# Zero_V1_0.net
KiCad netlist of a schematic drawn in EAGLE
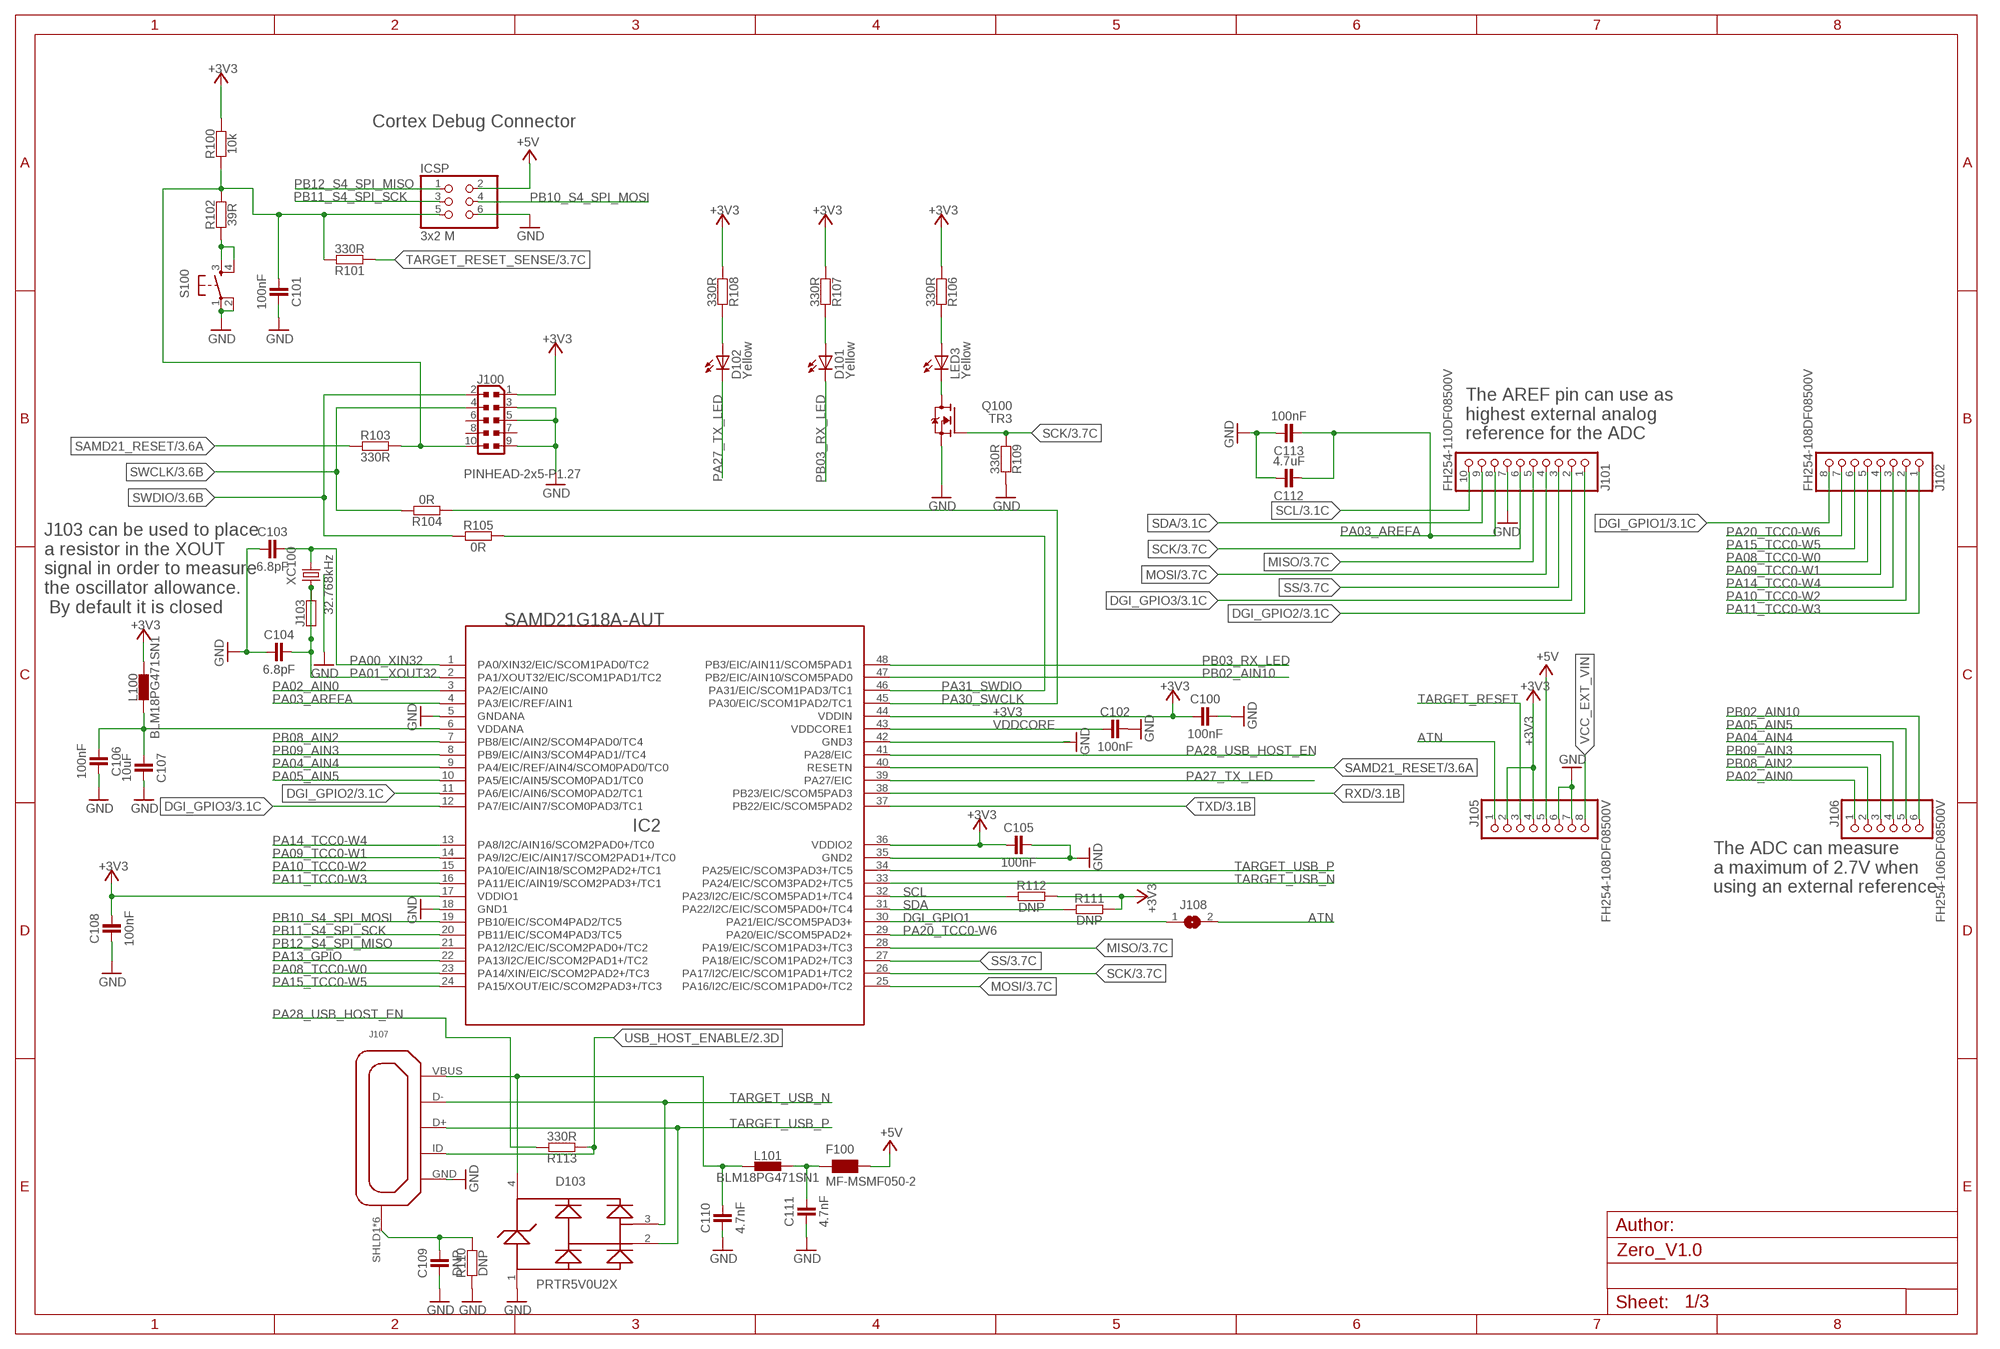
[diagram p0: schematic, sheet 1]
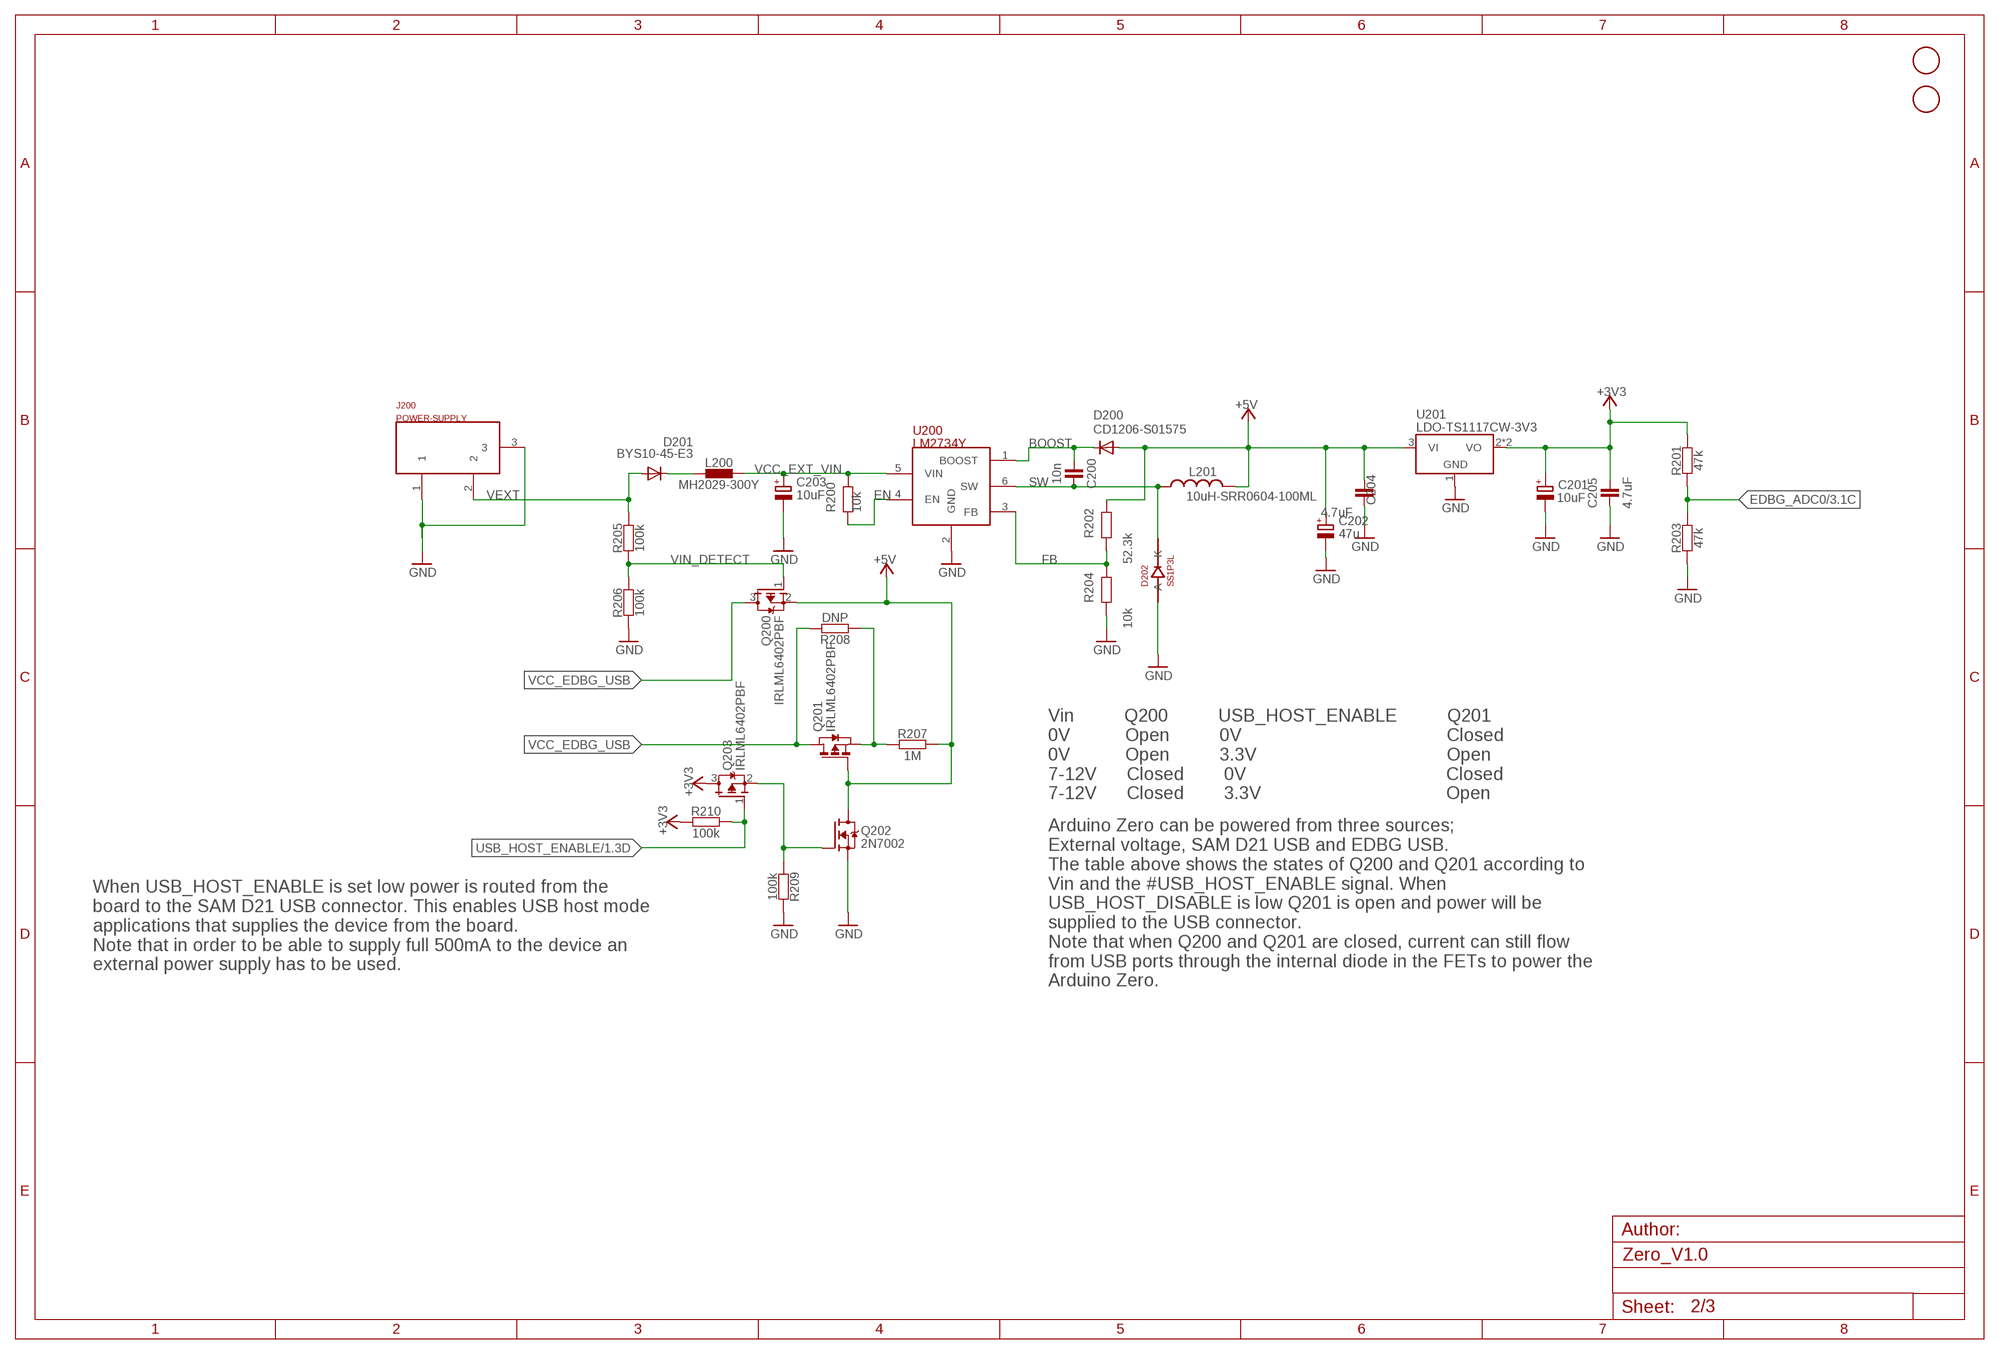
[diagram p1: schematic, sheet 2]
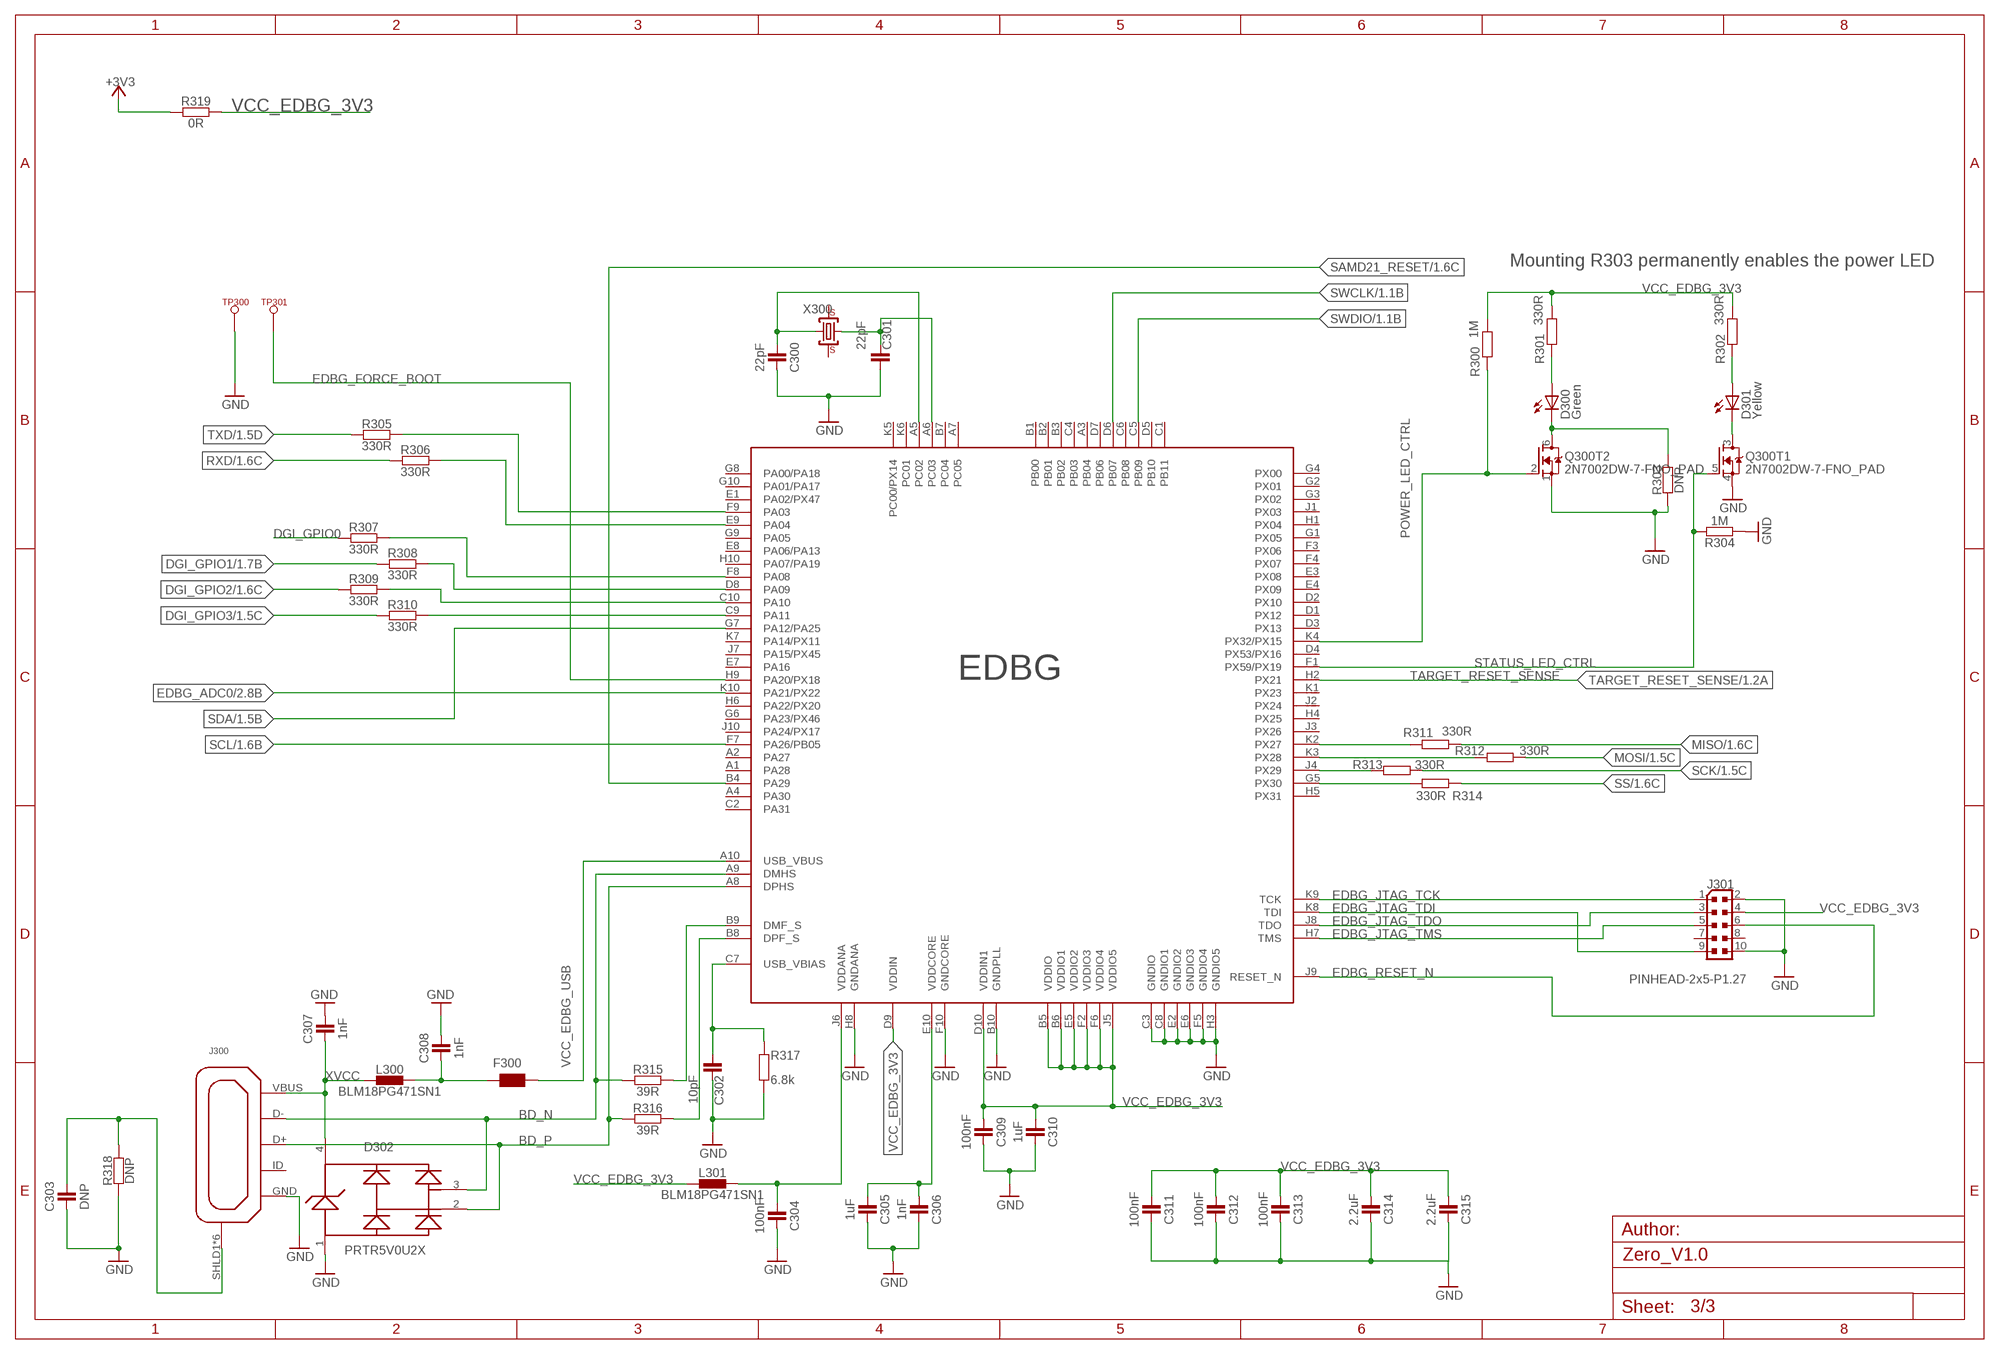
[diagram p2: schematic, sheet 3]

(export (version "E")
  (design (tool "Eeschema 10.0.6"))
  (components
    (comp (ref "C200")
      (value "10n")
      (footprint "eagle-import:C0402")
      (libsource (lib "eagle-import") (part "CAPACITORS-0402"))
    )
    (comp (ref "C201")
      (value "10uF")
      (footprint "eagle-import:PANASONIC_D")
      (fields (field (name "PART_NUMBER") "47uF"))
      (libsource (lib "eagle-import") (part "0113_47UF"))
    )
    (comp (ref "C202")
      (value "47u")
      (footprint "eagle-import:PANASONIC_D")
      (fields (field (name "PART_NUMBER") "47uF"))
      (libsource (lib "eagle-import") (part "0113_47UF"))
    )
    (comp (ref "C203")
      (value "10uF")
      (footprint "eagle-import:PANASONIC_D")
      (fields (field (name "PART_NUMBER") "47uF"))
      (libsource (lib "eagle-import") (part "0113_47UF"))
    )
    (comp (ref "C204")
      (value "4.7uF")
      (footprint "eagle-import:C0603")
      (libsource (lib "eagle-import") (part "CAPACITORS-0603"))
    )
    (comp (ref "C205")
      (value "4.7uF")
      (footprint "eagle-import:C0603")
      (libsource (lib "eagle-import") (part "CAPACITORS-0603"))
    )
    (comp (ref "D200")
      (value "CD1206-S01575")
      (footprint "eagle-import:MINIMELF")
      (libsource (lib "eagle-import") (part "0012_CD1206-S01575"))
    )
    (comp (ref "D201")
      (value "BYS10-45-E3")
      (footprint "eagle-import:MINIMELF")
      (fields (field (name "PART_NUMBER") "CD1206-S01575"))
      (libsource (lib "eagle-import") (part "0012_CD1206-S01575"))
    )
    (comp (ref "D202")
      (value "SS1P3L")
      (footprint "eagle-import:DO220AAL")
      (fields (field (name "PART_NUMBER") "SS1P3L-M3/84A"))
      (libsource (lib "eagle-import") (part "0025_SS1P3L-M3/84A"))
    )
    (comp (ref "FD1")
      (value "FIDUCIALMOUNT")
      (footprint "eagle-import:FIDUCIA-MOUNT")
      (libsource (lib "eagle-import") (part "FIDUCIALMOUNT"))
    )
    (comp (ref "FD2")
      (value "FIDUCIALMOUNT")
      (footprint "eagle-import:FIDUCIA-MOUNT")
      (libsource (lib "eagle-import") (part "FIDUCIALMOUNT"))
    )
    (comp (ref "J200")
      (value "POWER-SUPPLY")
      (footprint "eagle-import:POWERSUPPLY_DC-21MM")
      (fields (field (name "PART_NUMBER") "19746"))
      (libsource (lib "eagle-import") (part "0018_19746-POWER-SUPPLY"))
    )
    (comp (ref "L200")
      (value "MH2029-300Y")
      (footprint "eagle-import:C0805")
      (libsource (lib "eagle-import") (part "INDUCTOR-0805"))
    )
    (comp (ref "L201")
      (value "10uH-SRR0604-100ML")
      (footprint "eagle-import:SRR0604")
      (fields (field (name "PART_NUMBER") "SRR0604-100ML"))
      (libsource (lib "eagle-import") (part "0031_SRR0604-100ML"))
    )
    (comp (ref "Q200")
      (value "IRLML6402PBF")
      (footprint "eagle-import:SOT323")
      (libsource (lib "eagle-import") (part "IRLML6402PBF"))
    )
    (comp (ref "Q201")
      (value "IRLML6402PBF")
      (footprint "eagle-import:SOT-23")
      (fields (field (name "PART_NUMBER") "PMV48XP"))
      (libsource (lib "eagle-import") (part "0297_PMV48XP"))
    )
    (comp (ref "Q202")
      (value "2N7002")
      (footprint "eagle-import:SOT23")
      (libsource (lib "eagle-import") (part "MOSFET-N-SOT23"))
    )
    (comp (ref "Q203")
      (value "IRLML6402PBF")
      (footprint "eagle-import:SOT323")
      (libsource (lib "eagle-import") (part "IRLML6402PBF"))
    )
    (comp (ref "R200")
      (value "10k")
      (footprint "eagle-import:C0402")
      (libsource (lib "eagle-import") (part "RESISTORS-0402"))
    )
    (comp (ref "R201")
      (value "47k")
      (footprint "eagle-import:C0402")
      (libsource (lib "eagle-import") (part "RESISTORS-0402"))
    )
    (comp (ref "R202")
      (value "52.3k")
      (footprint "eagle-import:C0402")
      (libsource (lib "eagle-import") (part "RESISTORS-0402"))
    )
    (comp (ref "R203")
      (value "47k")
      (footprint "eagle-import:C0402")
      (libsource (lib "eagle-import") (part "RESISTORS-0402"))
    )
    (comp (ref "R204")
      (value "10k")
      (footprint "eagle-import:C0402")
      (libsource (lib "eagle-import") (part "RESISTORS-0402"))
    )
    (comp (ref "R205")
      (value "100k")
      (footprint "eagle-import:C0402")
      (libsource (lib "eagle-import") (part "RESISTORS-0402"))
    )
    (comp (ref "R206")
      (value "100k")
      (footprint "eagle-import:C0402")
      (libsource (lib "eagle-import") (part "RESISTORS-0402"))
    )
    (comp (ref "R207")
      (value "1M")
      (footprint "eagle-import:C0402")
      (libsource (lib "eagle-import") (part "RESISTORS-0402"))
    )
    (comp (ref "R208")
      (value "DNP")
      (footprint "eagle-import:C0402")
      (libsource (lib "eagle-import") (part "RESISTORS-0402"))
    )
    (comp (ref "R209")
      (value "100k")
      (footprint "eagle-import:C0402")
      (libsource (lib "eagle-import") (part "RESISTORS-0402"))
    )
    (comp (ref "R210")
      (value "100k")
      (footprint "eagle-import:C0402")
      (libsource (lib "eagle-import") (part "RESISTORS-0402"))
    )
    (comp (ref "U200")
      (value "LM2734Y")
      (footprint "eagle-import:SOT23-6")
      (fields (field (name "PART_NUMBER") "LM2734YMK"))
      (libsource (lib "eagle-import") (part "0179_LM2734YMK"))
    )
    (comp (ref "U201")
      (value "LDO-TS1117CW-3V3")
      (footprint "eagle-import:SOT223")
      (libsource (lib "eagle-import") (part "LDO-TS1117CW-3V3"))
    )
    (comp (ref "C100")
      (value "100nF")
      (footprint "eagle-import:C0402")
      (libsource (lib "eagle-import") (part "CAPACITORS-0402"))
    )
    (comp (ref "C101")
      (value "100nF")
      (footprint "eagle-import:C0402")
      (libsource (lib "eagle-import") (part "CAPACITORS-0402"))
    )
    (comp (ref "C102")
      (value "100nF")
      (footprint "eagle-import:C0402")
      (libsource (lib "eagle-import") (part "CAPACITORS-0402"))
    )
    (comp (ref "C103")
      (value "6.8pF")
      (footprint "eagle-import:C0402")
      (libsource (lib "eagle-import") (part "CAPACITORS-0402"))
    )
    (comp (ref "C104")
      (value "6.8pF")
      (footprint "eagle-import:C0402")
      (libsource (lib "eagle-import") (part "CAPACITORS-0402"))
    )
    (comp (ref "C105")
      (value "100nF")
      (footprint "eagle-import:C0402")
      (libsource (lib "eagle-import") (part "CAPACITORS-0402"))
    )
    (comp (ref "C106")
      (value "100nF")
      (footprint "eagle-import:C0402")
      (libsource (lib "eagle-import") (part "CAPACITORS-0402"))
    )
    (comp (ref "C107")
      (value "10uF")
      (footprint "eagle-import:C0603")
      (libsource (lib "eagle-import") (part "CAPACITORS-0603"))
    )
    (comp (ref "C108")
      (value "100nF")
      (footprint "eagle-import:C0402")
      (libsource (lib "eagle-import") (part "CAPACITORS-0402"))
    )
    (comp (ref "C109")
      (value "DNP")
      (footprint "eagle-import:C0402")
      (libsource (lib "eagle-import") (part "CAPACITORS-0402"))
    )
    (comp (ref "C110")
      (value "4.7nF")
      (footprint "eagle-import:C0402")
      (libsource (lib "eagle-import") (part "CAPACITORS-0402"))
    )
    (comp (ref "C111")
      (value "4.7nF")
      (footprint "eagle-import:C0402")
      (libsource (lib "eagle-import") (part "CAPACITORS-0402"))
    )
    (comp (ref "C112")
      (value "4.7uF")
      (footprint "eagle-import:C0603")
      (libsource (lib "eagle-import") (part "CAPACITORS-0603"))
    )
    (comp (ref "C113")
      (value "100nF")
      (footprint "eagle-import:C0402")
      (libsource (lib "eagle-import") (part "CAPACITORS-0402"))
    )
    (comp (ref "D101")
      (value "Yellow")
      (footprint "eagle-import:CHIPLED_0805")
      (fields (field (name "PART_NUMBER") "KPT-2012YC"))
      (libsource (lib "eagle-import") (part "0044_KPT-2012YC"))
    )
    (comp (ref "D102")
      (value "Yellow")
      (footprint "eagle-import:CHIPLED_0805")
      (fields (field (name "PART_NUMBER") "KPT-2012YC"))
      (libsource (lib "eagle-import") (part "0044_KPT-2012YC"))
    )
    (comp (ref "D103")
      (value "PRTR5V0U2XB")
      (footprint "eagle-import:SOT143B")
      (libsource (lib "eagle-import") (part "PRTR5V0U2XB"))
    )
    (comp (ref "F100")
      (value "MF-MSMF050-2")
      (footprint "eagle-import:WUERTH-ELEKTRONIK_1812")
      (libsource (lib "eagle-import") (part "WUERTH-ELEKTRONIK_WE-CBF_1812"))
    )
    (comp (ref "IC2")
      (value "SAMD21G18A-AUT")
      (footprint "eagle-import:TQFP48")
      (libsource (lib "eagle-import") (part "SAMD21G18A"))
    )
    (comp (ref "ICSP")
      (value "3x2 M")
      (footprint "eagle-import:2X03")
      (libsource (lib "eagle-import") (part "ICSP"))
    )
    (comp (ref "J100")
      (value "PINHEAD-2x5-P1.27")
      (footprint "eagle-import:PINHEAD_2X05_127")
      (libsource (lib "eagle-import") (part "0171_PH127-205DF055G00AROUND-PADS"))
    )
    (comp (ref "J101")
      (value "FH254-110DF08500V")
      (footprint "eagle-import:1X10")
      (fields (field (name "PART_NUMBER") "20TW-537"))
      (libsource (lib "eagle-import") (part "1684_20TW-537"))
    )
    (comp (ref "J102")
      (value "FH254-108DF08500V")
      (footprint "eagle-import:1X08")
      (fields (field (name "PART_NUMBER") "20TW-536"))
      (libsource (lib "eagle-import") (part "1683_20TW-536"))
    )
    (comp (ref "J103")
      (value "RESISTORS-0402")
      (footprint "eagle-import:C0402")
      (libsource (lib "eagle-import") (part "RESISTORS-0402"))
    )
    (comp (ref "J105")
      (value "FH254-108DF08500V")
      (footprint "eagle-import:1X08")
      (fields (field (name "PART_NUMBER") "20TW-536"))
      (libsource (lib "eagle-import") (part "1683_20TW-536"))
    )
    (comp (ref "J106")
      (value "FH254-106DF08500V")
      (footprint "eagle-import:1X06")
      (fields (field (name "PART_NUMBER") "20TW-535"))
      (libsource (lib "eagle-import") (part "1682_20TW-535_STD"))
    )
    (comp (ref "J107")
      (value "ZX62-AB-5PA")
      (footprint "eagle-import:USB-MICRO-10103594")
      (libsource (lib "eagle-import") (part "ZX62-AB-5PA"))
    )
    (comp (ref "J108")
      (value "SJ")
      (footprint "eagle-import:SJ")
      (libsource (lib "eagle-import") (part "SJ"))
    )
    (comp (ref "L100")
      (value "BLM18PG471SN1")
      (footprint "eagle-import:C0603")
      (libsource (lib "eagle-import") (part "INDUCTOR-0603"))
    )
    (comp (ref "L101")
      (value "BLM18PG471SN1")
      (footprint "eagle-import:C0603")
      (libsource (lib "eagle-import") (part "INDUCTOR-0603"))
    )
    (comp (ref "LED3")
      (value "Yellow")
      (footprint "eagle-import:CHIPLED_0805")
      (fields (field (name "PART_NUMBER") "KPT-2012YC"))
      (libsource (lib "eagle-import") (part "0044_KPT-2012YC"))
    )
    (comp (ref "R100")
      (value "10k")
      (footprint "eagle-import:C0402")
      (libsource (lib "eagle-import") (part "RESISTORS-0402"))
    )
    (comp (ref "R101")
      (value "330R")
      (footprint "eagle-import:C0402")
      (libsource (lib "eagle-import") (part "RESISTORS-0402"))
    )
    (comp (ref "R102")
      (value "39R")
      (footprint "eagle-import:C0402")
      (libsource (lib "eagle-import") (part "RESISTORS-0402"))
    )
    (comp (ref "R103")
      (value "330R")
      (footprint "eagle-import:C0402")
      (libsource (lib "eagle-import") (part "RESISTORS-0402"))
    )
    (comp (ref "R104")
      (value "0R")
      (footprint "eagle-import:C0402")
      (libsource (lib "eagle-import") (part "RESISTORS-0402"))
    )
    (comp (ref "R105")
      (value "0R")
      (footprint "eagle-import:C0402")
      (libsource (lib "eagle-import") (part "RESISTORS-0402"))
    )
    (comp (ref "R106")
      (value "330R")
      (footprint "eagle-import:C0402")
      (libsource (lib "eagle-import") (part "RESISTORS-0402"))
    )
    (comp (ref "R107")
      (value "330R")
      (footprint "eagle-import:C0402")
      (libsource (lib "eagle-import") (part "RESISTORS-0402"))
    )
    (comp (ref "R108")
      (value "330R")
      (footprint "eagle-import:C0402")
      (libsource (lib "eagle-import") (part "RESISTORS-0402"))
    )
    (comp (ref "R109")
      (value "330R")
      (footprint "eagle-import:C0402")
      (libsource (lib "eagle-import") (part "RESISTORS-0402"))
    )
    (comp (ref "R110")
      (value "DNP")
      (footprint "eagle-import:C0402")
      (libsource (lib "eagle-import") (part "RESISTORS-0402"))
    )
    (comp (ref "R111")
      (value "DNP")
      (footprint "eagle-import:C0402")
      (libsource (lib "eagle-import") (part "RESISTORS-0402"))
    )
    (comp (ref "R112")
      (value "DNP")
      (footprint "eagle-import:C0402")
      (libsource (lib "eagle-import") (part "RESISTORS-0402"))
    )
    (comp (ref "R113")
      (value "330R")
      (footprint "eagle-import:C0402")
      (libsource (lib "eagle-import") (part "RESISTORS-0402"))
    )
    (comp (ref "S100")
      (value "PUSHBUTTON3")
      (footprint "eagle-import:TS42_4PINS")
      (libsource (lib "eagle-import") (part "PUSHBUTTON3"))
    )
    (comp (ref "TR3")
      (value "Q100")
      (footprint "eagle-import:SOT-23")
      (libsource (lib "eagle-import") (part "1612_2N7002LT1G"))
    )
    (comp (ref "XC100")
      (value "32.768kHz")
      (footprint "eagle-import:CRYSTAL_TC26SMD")
      (libsource (lib "eagle-import") (part "CRYSTALSMD"))
    )
    (comp (ref "C300")
      (value "22pF")
      (footprint "eagle-import:C0402")
      (libsource (lib "eagle-import") (part "CAPACITORS-0402"))
    )
    (comp (ref "C301")
      (value "22pF")
      (footprint "eagle-import:C0402")
      (libsource (lib "eagle-import") (part "CAPACITORS-0402"))
    )
    (comp (ref "C302")
      (value "10pF")
      (footprint "eagle-import:C0402")
      (libsource (lib "eagle-import") (part "CAPACITORS-0402"))
    )
    (comp (ref "C303")
      (value "DNP")
      (footprint "eagle-import:C0402")
      (libsource (lib "eagle-import") (part "CAPACITORS-0402"))
    )
    (comp (ref "C304")
      (value "100nF")
      (footprint "eagle-import:C0402")
      (libsource (lib "eagle-import") (part "CAPACITORS-0402"))
    )
    (comp (ref "C305")
      (value "1uF")
      (footprint "eagle-import:C0402")
      (libsource (lib "eagle-import") (part "CAPACITORS-0402"))
    )
    (comp (ref "C306")
      (value "1nF")
      (footprint "eagle-import:C0402")
      (libsource (lib "eagle-import") (part "CAPACITORS-0402"))
    )
    (comp (ref "C307")
      (value "1nF")
      (footprint "eagle-import:C0402")
      (libsource (lib "eagle-import") (part "CAPACITORS-0402"))
    )
    (comp (ref "C308")
      (value "1nF")
      (footprint "eagle-import:C0402")
      (libsource (lib "eagle-import") (part "CAPACITORS-0402"))
    )
    (comp (ref "C309")
      (value "100nF")
      (footprint "eagle-import:C0402")
      (libsource (lib "eagle-import") (part "CAPACITORS-0402"))
    )
    (comp (ref "C310")
      (value "1uF")
      (footprint "eagle-import:C0402")
      (libsource (lib "eagle-import") (part "CAPACITORS-0402"))
    )
    (comp (ref "C311")
      (value "100nF")
      (footprint "eagle-import:C0402")
      (libsource (lib "eagle-import") (part "CAPACITORS-0402"))
    )
    (comp (ref "C312")
      (value "100nF")
      (footprint "eagle-import:C0402")
      (libsource (lib "eagle-import") (part "CAPACITORS-0402"))
    )
    (comp (ref "C313")
      (value "100nF")
      (footprint "eagle-import:C0402")
      (libsource (lib "eagle-import") (part "CAPACITORS-0402"))
    )
    (comp (ref "C314")
      (value "2.2uF")
      (footprint "eagle-import:C0402")
      (libsource (lib "eagle-import") (part "CAPACITORS-0402"))
    )
    (comp (ref "C315")
      (value "2.2uF")
      (footprint "eagle-import:C0402")
      (libsource (lib "eagle-import") (part "CAPACITORS-0402"))
    )
    (comp (ref "D300")
      (value "Green")
      (footprint "eagle-import:CHIPLED_0805")
      (fields (field (name "PART_NUMBER") "KPT-2012SGC"))
      (libsource (lib "eagle-import") (part "0043_KPT-2012SGC"))
    )
    (comp (ref "D301")
      (value "Yellow")
      (footprint "eagle-import:CHIPLED_0805")
      (fields (field (name "PART_NUMBER") "KPT-2012SGC"))
      (libsource (lib "eagle-import") (part "0043_KPT-2012SGC"))
    )
    (comp (ref "D302")
      (value "PRTR5V0U2XB")
      (footprint "eagle-import:SOT143B")
      (libsource (lib "eagle-import") (part "PRTR5V0U2XB"))
    )
    (comp (ref "EDBG")
      (value "EDBG")
      (footprint "eagle-import:VFBGA100")
      (libsource (lib "eagle-import") (part "EDBG"))
    )
    (comp (ref "F300")
      (value "WUERTH-ELEKTRONIK_WE-CBF_1812")
      (footprint "eagle-import:WUERTH-ELEKTRONIK_1812")
      (libsource (lib "eagle-import") (part "WUERTH-ELEKTRONIK_WE-CBF_1812"))
    )
    (comp (ref "J300")
      (value "ZX62-AB-5PA")
      (footprint "eagle-import:USB-MICRO-10103594")
      (libsource (lib "eagle-import") (part "ZX62-AB-5PA"))
    )
    (comp (ref "J301")
      (value "PINHEAD-2x5-P1.27")
      (footprint "eagle-import:PINHEAD_2X05_127")
      (libsource (lib "eagle-import") (part "0171_PH127-205DF055G00AROUND-PADS"))
    )
    (comp (ref "L300")
      (value "BLM18PG471SN1")
      (footprint "eagle-import:C0603")
      (libsource (lib "eagle-import") (part "INDUCTOR-0603"))
    )
    (comp (ref "L301")
      (value "BLM18PG471SN1")
      (footprint "eagle-import:C0603")
      (libsource (lib "eagle-import") (part "INDUCTOR-0603"))
    )
    (comp (ref "Q300")
      (value "2N7002DW-7-FNO_PAD")
      (footprint "eagle-import:PWR_SC70-6L2")
      (libsource (lib "eagle-import") (part "2N7002DW-7-FNO_PAD"))
    )
    (comp (ref "R300")
      (value "1M")
      (footprint "eagle-import:C0402")
      (libsource (lib "eagle-import") (part "RESISTORS-0402"))
    )
    (comp (ref "R301")
      (value "330R")
      (footprint "eagle-import:C0402")
      (libsource (lib "eagle-import") (part "RESISTORS-0402"))
    )
    (comp (ref "R302")
      (value "330R")
      (footprint "eagle-import:C0402")
      (libsource (lib "eagle-import") (part "RESISTORS-0402"))
    )
    (comp (ref "R303")
      (value "DNP")
      (footprint "eagle-import:C0402")
      (libsource (lib "eagle-import") (part "RESISTORS-0402"))
    )
    (comp (ref "R304")
      (value "1M")
      (footprint "eagle-import:C0402")
      (libsource (lib "eagle-import") (part "RESISTORS-0402"))
    )
    (comp (ref "R305")
      (value "330R")
      (footprint "eagle-import:C0402")
      (libsource (lib "eagle-import") (part "RESISTORS-0402"))
    )
    (comp (ref "R306")
      (value "330R")
      (footprint "eagle-import:C0402")
      (libsource (lib "eagle-import") (part "RESISTORS-0402"))
    )
    (comp (ref "R307")
      (value "330R")
      (footprint "eagle-import:C0402")
      (libsource (lib "eagle-import") (part "RESISTORS-0402"))
    )
    (comp (ref "R308")
      (value "330R")
      (footprint "eagle-import:C0402")
      (libsource (lib "eagle-import") (part "RESISTORS-0402"))
    )
    (comp (ref "R309")
      (value "330R")
      (footprint "eagle-import:C0402")
      (libsource (lib "eagle-import") (part "RESISTORS-0402"))
    )
    (comp (ref "R310")
      (value "330R")
      (footprint "eagle-import:C0402")
      (libsource (lib "eagle-import") (part "RESISTORS-0402"))
    )
    (comp (ref "R311")
      (value "330R")
      (footprint "eagle-import:C0402")
      (libsource (lib "eagle-import") (part "RESISTORS-0402"))
    )
    (comp (ref "R312")
      (value "330R")
      (footprint "eagle-import:C0402")
      (libsource (lib "eagle-import") (part "RESISTORS-0402"))
    )
    (comp (ref "R313")
      (value "330R")
      (footprint "eagle-import:C0402")
      (libsource (lib "eagle-import") (part "RESISTORS-0402"))
    )
    (comp (ref "R314")
      (value "330R")
      (footprint "eagle-import:C0402")
      (libsource (lib "eagle-import") (part "RESISTORS-0402"))
    )
    (comp (ref "R315")
      (value "39R")
      (footprint "eagle-import:C0402")
      (libsource (lib "eagle-import") (part "RESISTORS-0402"))
    )
    (comp (ref "R316")
      (value "39R")
      (footprint "eagle-import:C0402")
      (libsource (lib "eagle-import") (part "RESISTORS-0402"))
    )
    (comp (ref "R317")
      (value "6.8k")
      (footprint "eagle-import:C0402")
      (libsource (lib "eagle-import") (part "RESISTORS-0402"))
    )
    (comp (ref "R318")
      (value "DNP")
      (footprint "eagle-import:C0402")
      (libsource (lib "eagle-import") (part "RESISTORS-0402"))
    )
    (comp (ref "R319")
      (value "0R")
      (footprint "eagle-import:C0402")
      (libsource (lib "eagle-import") (part "RESISTORS-0402"))
    )
    (comp (ref "TP300")
      (value "TP_SP")
      (footprint "eagle-import:TP-SP")
      (libsource (lib "eagle-import") (part "TP_SP"))
    )
    (comp (ref "TP301")
      (value "TP_SP")
      (footprint "eagle-import:TP-SP")
      (libsource (lib "eagle-import") (part "TP_SP"))
    )
    (comp (ref "X300")
      (value "12mHz-12pF-K7")
      (footprint "eagle-import:CRYSTAL-5.4-3.2")
      (libsource (lib "eagle-import") (part "12MHZ-12PF-K75.4-3.2"))
    )
  )
  (nets
    (net (code "1") (name "+3V3") (class "Default")
      (node (ref "C100") (pin "1") (pinfunction "1_1") (pintype "passive"))
      (node (ref "C105") (pin "1") (pinfunction "1_1") (pintype "passive"))
      (node (ref "C108") (pin "2") (pinfunction "2_2") (pintype "passive"))
      (node (ref "C201") (pin "+") (pinfunction "+_+") (pintype "passive"))
      (node (ref "C205") (pin "2") (pinfunction "2_2") (pintype "passive"))
      (node (ref "IC2") (pin "17") (pinfunction "VDDIO1_17") (pintype "power_in"))
      (node (ref "IC2") (pin "36") (pinfunction "VDDIO2_36") (pintype "power_in"))
      (node (ref "IC2") (pin "44") (pinfunction "VDDIN_44") (pintype "power_in"))
      (node (ref "J100") (pin "1") (pinfunction "1_1") (pintype "passive"))
      (node (ref "J105") (pin "2") (pinfunction "2_2") (pintype "passive"))
      (node (ref "J105") (pin "4") (pinfunction "4_4") (pintype "passive"))
      (node (ref "L100") (pin "2") (pinfunction "2_2") (pintype "passive"))
      (node (ref "Q203") (pin "3") (pinfunction "D_3") (pintype "passive"))
      (node (ref "R100") (pin "2") (pinfunction "2_2") (pintype "passive"))
      (node (ref "R106") (pin "1") (pinfunction "1_1") (pintype "passive"))
      (node (ref "R107") (pin "1") (pinfunction "1_1") (pintype "passive"))
      (node (ref "R108") (pin "1") (pinfunction "1_1") (pintype "passive"))
      (node (ref "R111") (pin "2") (pinfunction "2_2") (pintype "passive"))
      (node (ref "R112") (pin "2") (pinfunction "2_2") (pintype "passive"))
      (node (ref "R201") (pin "2") (pinfunction "2_2") (pintype "passive"))
      (node (ref "R210") (pin "1") (pinfunction "1_1") (pintype "passive"))
      (node (ref "R319") (pin "1") (pinfunction "1_1") (pintype "passive"))
      (node (ref "U201") (pin "2") (pinfunction "VO_2") (pintype "passive"))
      (node (ref "U201") (pin "4") (pinfunction "VO_4") (pintype "passive"))
    )
    (net (code "2") (name "+5V") (class "Default")
      (node (ref "C202") (pin "+") (pinfunction "+_+") (pintype "passive"))
      (node (ref "C204") (pin "1") (pinfunction "1_1") (pintype "passive"))
      (node (ref "D200") (pin "A") (pinfunction "A_A") (pintype "passive"))
      (node (ref "F100") (pin "2") (pinfunction "2_2") (pintype "passive"))
      (node (ref "ICSP") (pin "2") (pinfunction "2_2") (pintype "passive"))
      (node (ref "J105") (pin "5") (pinfunction "5_5") (pintype "passive"))
      (node (ref "L201") (pin "P$2") (pinfunction "2_P$2") (pintype "passive"))
      (node (ref "Q200") (pin "2") (pinfunction "S_2") (pintype "passive"))
      (node (ref "Q201") (pin "3") (pinfunction "G_3") (pintype "passive"))
      (node (ref "Q202") (pin "3") (pinfunction "D_3") (pintype "passive"))
      (node (ref "R202") (pin "1") (pinfunction "1_1") (pintype "passive"))
      (node (ref "R207") (pin "2") (pinfunction "2_2") (pintype "passive"))
      (node (ref "U201") (pin "3") (pinfunction "VI_3") (pintype "input"))
    )
    (net (code "3") (name "ATN") (class "Default")
      (node (ref "J105") (pin "1") (pinfunction "1_1") (pintype "passive"))
      (node (ref "J108") (pin "2") (pinfunction "2_2") (pintype "passive"))
    )
    (net (code "4") (name "BD_N") (class "Default")
      (node (ref "D302") (pin "3") (pinfunction "3_3") (pintype "bidirectional"))
      (node (ref "EDBG") (pin "A9") (pinfunction "DMHS_A9") (pintype "bidirectional"))
      (node (ref "J300") (pin "D-") (pinfunction "D-_D-") (pintype "bidirectional"))
      (node (ref "R315") (pin "1") (pinfunction "1_1") (pintype "passive"))
    )
    (net (code "5") (name "BD_P") (class "Default")
      (node (ref "D302") (pin "2") (pinfunction "2_2") (pintype "bidirectional"))
      (node (ref "EDBG") (pin "A8") (pinfunction "DPHS_A8") (pintype "bidirectional"))
      (node (ref "J300") (pin "D+") (pinfunction "D+_D+") (pintype "bidirectional"))
      (node (ref "R316") (pin "1") (pinfunction "1_1") (pintype "passive"))
    )
    (net (code "6") (name "BOOST") (class "Default")
      (node (ref "C200") (pin "1") (pinfunction "1_1") (pintype "passive"))
      (node (ref "D200") (pin "C") (pinfunction "C_C") (pintype "passive"))
      (node (ref "U200") (pin "1") (pinfunction "BOOST_1") (pintype "input"))
    )
    (net (code "7") (name "DGI_GPIO0") (class "Default")
      (node (ref "R307") (pin "1") (pinfunction "1_1") (pintype "passive"))
    )
    (net (code "8") (name "DGI_GPIO1") (class "Default")
      (node (ref "IC2") (pin "30") (pinfunction "PA21/EIC/SCOM5PAD3+_30") (pintype "bidirectional"))
      (node (ref "J102") (pin "8") (pinfunction "8_8") (pintype "passive"))
      (node (ref "J108") (pin "1") (pinfunction "1_1") (pintype "passive"))
      (node (ref "R308") (pin "1") (pinfunction "1_1") (pintype "passive"))
    )
    (net (code "9") (name "DGI_GPIO2") (class "Default")
      (node (ref "IC2") (pin "11") (pinfunction "PA6/EIC/AIN6/SCOM0PAD2/TC1_11") (pintype "bidirectional"))
      (node (ref "J101") (pin "1") (pinfunction "1_1") (pintype "passive"))
      (node (ref "R309") (pin "1") (pinfunction "1_1") (pintype "passive"))
    )
    (net (code "10") (name "DGI_GPIO3") (class "Default")
      (node (ref "IC2") (pin "12") (pinfunction "PA7/EIC/AIN7/SCOM0PAD3/TC1_12") (pintype "bidirectional"))
      (node (ref "J101") (pin "2") (pinfunction "2_2") (pintype "passive"))
      (node (ref "R310") (pin "1") (pinfunction "1_1") (pintype "passive"))
    )
    (net (code "11") (name "EDBG_ADC0") (class "Default")
      (node (ref "EDBG") (pin "K10") (pinfunction "PA21/PX22_K10") (pintype "bidirectional"))
      (node (ref "R201") (pin "1") (pinfunction "1_1") (pintype "passive"))
      (node (ref "R203") (pin "2") (pinfunction "2_2") (pintype "passive"))
    )
    (net (code "12") (name "EDBG_FORCE_BOOT") (class "Default")
      (node (ref "EDBG") (pin "H9") (pinfunction "PA20/PX18_H9") (pintype "bidirectional"))
      (node (ref "TP301") (pin "X") (pinfunction "TESTP_X") (pintype "passive"))
    )
    (net (code "13") (name "EDBG_JTAG_TCK") (class "Default")
      (node (ref "EDBG") (pin "K9") (pinfunction "TCK_K9") (pintype "bidirectional"))
      (node (ref "J301") (pin "1") (pinfunction "1_1") (pintype "passive"))
    )
    (net (code "14") (name "EDBG_JTAG_TDI") (class "Default")
      (node (ref "EDBG") (pin "K8") (pinfunction "TDI_K8") (pintype "bidirectional"))
      (node (ref "J301") (pin "9") (pinfunction "9_9") (pintype "passive"))
    )
    (net (code "15") (name "EDBG_JTAG_TDO") (class "Default")
      (node (ref "EDBG") (pin "J8") (pinfunction "TDO_J8") (pintype "bidirectional"))
      (node (ref "J301") (pin "3") (pinfunction "3_3") (pintype "passive"))
    )
    (net (code "16") (name "EDBG_JTAG_TMS") (class "Default")
      (node (ref "EDBG") (pin "H7") (pinfunction "TMS_H7") (pintype "bidirectional"))
      (node (ref "J301") (pin "5") (pinfunction "5_5") (pintype "passive"))
    )
    (net (code "17") (name "EDBG_RESET_N") (class "Default")
      (node (ref "EDBG") (pin "J9") (pinfunction "RESET_N_J9") (pintype "bidirectional"))
      (node (ref "J301") (pin "6") (pinfunction "6_6") (pintype "passive"))
    )
    (net (code "18") (name "EN") (class "Default")
      (node (ref "R200") (pin "2") (pinfunction "2_2") (pintype "passive"))
      (node (ref "U200") (pin "4") (pinfunction "EN_4") (pintype "input"))
    )
    (net (code "19") (name "FB") (class "Default")
      (node (ref "R202") (pin "2") (pinfunction "2_2") (pintype "passive"))
      (node (ref "R204") (pin "1") (pinfunction "1_1") (pintype "passive"))
      (node (ref "U200") (pin "3") (pinfunction "FB_3") (pintype "input"))
    )
    (net (code "20") (name "GND") (class "Default")
      (node (ref "C100") (pin "2") (pinfunction "2_2") (pintype "passive"))
      (node (ref "C101") (pin "2") (pinfunction "2_2") (pintype "passive"))
      (node (ref "C102") (pin "2") (pinfunction "2_2") (pintype "passive"))
      (node (ref "C103") (pin "1") (pinfunction "1_1") (pintype "passive"))
      (node (ref "C104") (pin "1") (pinfunction "1_1") (pintype "passive"))
      (node (ref "C105") (pin "2") (pinfunction "2_2") (pintype "passive"))
      (node (ref "C106") (pin "2") (pinfunction "2_2") (pintype "passive"))
      (node (ref "C107") (pin "2") (pinfunction "2_2") (pintype "passive"))
      (node (ref "C108") (pin "1") (pinfunction "1_1") (pintype "passive"))
      (node (ref "C109") (pin "1") (pinfunction "1_1") (pintype "passive"))
      (node (ref "C110") (pin "1") (pinfunction "1_1") (pintype "passive"))
      (node (ref "C111") (pin "1") (pinfunction "1_1") (pintype "passive"))
      (node (ref "C112") (pin "2") (pinfunction "2_2") (pintype "passive"))
      (node (ref "C113") (pin "2") (pinfunction "2_2") (pintype "passive"))
      (node (ref "C201") (pin "-") (pinfunction "-_-") (pintype "passive"))
      (node (ref "C202") (pin "-") (pinfunction "-_-") (pintype "passive"))
      (node (ref "C203") (pin "-") (pinfunction "-_-") (pintype "passive"))
      (node (ref "C204") (pin "2") (pinfunction "2_2") (pintype "passive"))
      (node (ref "C205") (pin "1") (pinfunction "1_1") (pintype "passive"))
      (node (ref "C300") (pin "2") (pinfunction "2_2") (pintype "passive"))
      (node (ref "C301") (pin "2") (pinfunction "2_2") (pintype "passive"))
      (node (ref "C302") (pin "2") (pinfunction "2_2") (pintype "passive"))
      (node (ref "C303") (pin "1") (pinfunction "1_1") (pintype "passive"))
      (node (ref "C304") (pin "2") (pinfunction "2_2") (pintype "passive"))
      (node (ref "C305") (pin "2") (pinfunction "2_2") (pintype "passive"))
      (node (ref "C306") (pin "2") (pinfunction "2_2") (pintype "passive"))
      (node (ref "C307") (pin "2") (pinfunction "2_2") (pintype "passive"))
      (node (ref "C308") (pin "2") (pinfunction "2_2") (pintype "passive"))
      (node (ref "C309") (pin "2") (pinfunction "2_2") (pintype "passive"))
      (node (ref "C310") (pin "2") (pinfunction "2_2") (pintype "passive"))
      (node (ref "C311") (pin "2") (pinfunction "2_2") (pintype "passive"))
      (node (ref "C312") (pin "2") (pinfunction "2_2") (pintype "passive"))
      (node (ref "C313") (pin "2") (pinfunction "2_2") (pintype "passive"))
      (node (ref "C314") (pin "2") (pinfunction "2_2") (pintype "passive"))
      (node (ref "C315") (pin "2") (pinfunction "2_2") (pintype "passive"))
      (node (ref "D103") (pin "1") (pinfunction "1_1") (pintype "bidirectional"))
      (node (ref "D202") (pin "P$2") (pinfunction "A_P$2") (pintype "bidirectional"))
      (node (ref "D302") (pin "1") (pinfunction "1_1") (pintype "bidirectional"))
      (node (ref "EDBG") (pin "B10") (pinfunction "GNDPLL_B10") (pintype "bidirectional"))
      (node (ref "EDBG") (pin "C3") (pinfunction "GNDIO_C3") (pintype "bidirectional"))
      (node (ref "EDBG") (pin "C8") (pinfunction "GNDIO1_C8") (pintype "bidirectional"))
      (node (ref "EDBG") (pin "E2") (pinfunction "GNDIO2_E2") (pintype "bidirectional"))
      (node (ref "EDBG") (pin "E6") (pinfunction "GNDIO3_E6") (pintype "bidirectional"))
      (node (ref "EDBG") (pin "F10") (pinfunction "GNDCORE_F10") (pintype "bidirectional"))
      (node (ref "EDBG") (pin "F5") (pinfunction "GNDIO4_F5") (pintype "bidirectional"))
      (node (ref "EDBG") (pin "H3") (pinfunction "GNDIO5_H3") (pintype "bidirectional"))
      (node (ref "EDBG") (pin "H8") (pinfunction "GNDANA_H8") (pintype "bidirectional"))
      (node (ref "IC2") (pin "18") (pinfunction "GND1_18") (pintype "power_in"))
      (node (ref "IC2") (pin "35") (pinfunction "GND2_35") (pintype "power_in"))
      (node (ref "IC2") (pin "42") (pinfunction "GND3_42") (pintype "power_in"))
      (node (ref "IC2") (pin "5") (pinfunction "GNDANA_5") (pintype "power_in"))
      (node (ref "ICSP") (pin "6") (pinfunction "6_6") (pintype "passive"))
      (node (ref "J100") (pin "3") (pinfunction "3_3") (pintype "passive"))
      (node (ref "J100") (pin "5") (pinfunction "5_5") (pintype "passive"))
      (node (ref "J100") (pin "9") (pinfunction "9_9") (pintype "passive"))
      (node (ref "J101") (pin "7") (pinfunction "7_7") (pintype "passive"))
      (node (ref "J105") (pin "6") (pinfunction "6_6") (pintype "passive"))
      (node (ref "J105") (pin "7") (pinfunction "7_7") (pintype "passive"))
      (node (ref "J107") (pin "GND") (pinfunction "GND_GND") (pintype "bidirectional"))
      (node (ref "J200") (pin "1") (pinfunction "1_1") (pintype "power_in"))
      (node (ref "J200") (pin "3") (pinfunction "3_3") (pintype "power_in"))
      (node (ref "J300") (pin "GND") (pinfunction "GND_GND") (pintype "bidirectional"))
      (node (ref "J301") (pin "10") (pinfunction "10_10") (pintype "passive"))
      (node (ref "J301") (pin "2") (pinfunction "2_2") (pintype "passive"))
      (node (ref "Q202") (pin "2") (pinfunction "S_2") (pintype "passive"))
      (node (ref "Q300") (pin "1") (pinfunction "S_1") (pintype "passive"))
      (node (ref "Q300") (pin "4") (pinfunction "S_4") (pintype "passive"))
      (node (ref "R109") (pin "2") (pinfunction "2_2") (pintype "passive"))
      (node (ref "R110") (pin "1") (pinfunction "1_1") (pintype "passive"))
      (node (ref "R203") (pin "1") (pinfunction "1_1") (pintype "passive"))
      (node (ref "R204") (pin "2") (pinfunction "2_2") (pintype "passive"))
      (node (ref "R206") (pin "1") (pinfunction "1_1") (pintype "passive"))
      (node (ref "R209") (pin "2") (pinfunction "2_2") (pintype "passive"))
      (node (ref "R303") (pin "1") (pinfunction "1_1") (pintype "passive"))
      (node (ref "R304") (pin "1") (pinfunction "1_1") (pintype "passive"))
      (node (ref "R317") (pin "1") (pinfunction "1_1") (pintype "passive"))
      (node (ref "R318") (pin "1") (pinfunction "1_1") (pintype "passive"))
      (node (ref "S100") (pin "1") (pinfunction "1_1") (pintype "passive"))
      (node (ref "S100") (pin "2") (pinfunction "2_2") (pintype "passive"))
      (node (ref "TP300") (pin "X") (pinfunction "TESTP_X") (pintype "passive"))
      (node (ref "TR3") (pin "2") (pinfunction "S_2") (pintype "passive"))
      (node (ref "U200") (pin "2") (pinfunction "GND_2") (pintype "power_in"))
      (node (ref "U201") (pin "1") (pinfunction "GND_1") (pintype "passive"))
      (node (ref "XC100") (pin "P$1") (pinfunction "GND_P$1") (pintype "bidirectional"))
    )
    (net (code "21") (name "MISO") (class "Default")
      (node (ref "IC2") (pin "28") (pinfunction "PA19/EIC/SCOM1PAD3+/TC3_28") (pintype "bidirectional"))
      (node (ref "J101") (pin "5") (pinfunction "5_5") (pintype "passive"))
      (node (ref "R311") (pin "2") (pinfunction "2_2") (pintype "passive"))
    )
    (net (code "22") (name "MOSI") (class "Default")
      (node (ref "IC2") (pin "25") (pinfunction "PA16/I2C/EIC/SCOM1PAD0+/TC2_25") (pintype "bidirectional"))
      (node (ref "J101") (pin "4") (pinfunction "4_4") (pintype "passive"))
      (node (ref "R312") (pin "2") (pinfunction "2_2") (pintype "passive"))
    )
    (net (code "23") (name "Net-(C109-Pad2)") (class "Default")
      (node (ref "C109") (pin "2") (pinfunction "2_2") (pintype "passive"))
      (node (ref "J107") (pin "SHLD1") (pinfunction "SH_SHLD1") (pintype "bidirectional"))
      (node (ref "J107") (pin "SHLD2") (pinfunction "SH_SHLD2") (pintype "bidirectional"))
      (node (ref "J107") (pin "SHLD3") (pinfunction "SH_SHLD3") (pintype "bidirectional"))
      (node (ref "J107") (pin "SHLD4") (pinfunction "SH_SHLD4") (pintype "bidirectional"))
      (node (ref "J107") (pin "SHLD5") (pinfunction "SH_SHLD5") (pintype "bidirectional"))
      (node (ref "J107") (pin "SHLD6") (pinfunction "SH_SHLD6") (pintype "bidirectional"))
      (node (ref "R110") (pin "2") (pinfunction "2_2") (pintype "passive"))
    )
    (net (code "24") (name "Net-(C111-Pad2)") (class "Default")
      (node (ref "C111") (pin "2") (pinfunction "2_2") (pintype "passive"))
      (node (ref "F100") (pin "1") (pinfunction "1_1") (pintype "passive"))
      (node (ref "L101") (pin "2") (pinfunction "2_2") (pintype "passive"))
    )
    (net (code "25") (name "Net-(C303-Pad2)") (class "Default")
      (node (ref "C303") (pin "2") (pinfunction "2_2") (pintype "passive"))
      (node (ref "J300") (pin "SHLD1") (pinfunction "SH_SHLD1") (pintype "bidirectional"))
      (node (ref "J300") (pin "SHLD2") (pinfunction "SH_SHLD2") (pintype "bidirectional"))
      (node (ref "J300") (pin "SHLD3") (pinfunction "SH_SHLD3") (pintype "bidirectional"))
      (node (ref "J300") (pin "SHLD4") (pinfunction "SH_SHLD4") (pintype "bidirectional"))
      (node (ref "J300") (pin "SHLD5") (pinfunction "SH_SHLD5") (pintype "bidirectional"))
      (node (ref "J300") (pin "SHLD6") (pinfunction "SH_SHLD6") (pintype "bidirectional"))
      (node (ref "R318") (pin "2") (pinfunction "2_2") (pintype "passive"))
    )
    (net (code "26") (name "Net-(C308-Pad1)") (class "Default")
      (node (ref "C308") (pin "1") (pinfunction "1_1") (pintype "passive"))
      (node (ref "F300") (pin "1") (pinfunction "1_1") (pintype "passive"))
      (node (ref "L300") (pin "2") (pinfunction "2_2") (pintype "passive"))
    )
    (net (code "27") (name "Net-(D101-PadA)") (class "Default")
      (node (ref "D101") (pin "A") (pinfunction "A_A") (pintype "passive"))
      (node (ref "R107") (pin "2") (pinfunction "2_2") (pintype "passive"))
    )
    (net (code "28") (name "Net-(D102-PadA)") (class "Default")
      (node (ref "D102") (pin "A") (pinfunction "A_A") (pintype "passive"))
      (node (ref "R108") (pin "2") (pinfunction "2_2") (pintype "passive"))
    )
    (net (code "29") (name "Net-(D201-PadC)") (class "Default")
      (node (ref "D201") (pin "C") (pinfunction "C_C") (pintype "passive"))
      (node (ref "L200") (pin "1") (pinfunction "1_1") (pintype "passive"))
    )
    (net (code "30") (name "Net-(D300-PadA)") (class "Default")
      (node (ref "D300") (pin "A") (pinfunction "A_A") (pintype "passive"))
      (node (ref "R301") (pin "1") (pinfunction "1_1") (pintype "passive"))
    )
    (net (code "31") (name "Net-(D301-PadA)") (class "Default")
      (node (ref "D301") (pin "A") (pinfunction "A_A") (pintype "passive"))
      (node (ref "R302") (pin "1") (pinfunction "1_1") (pintype "passive"))
    )
    (net (code "32") (name "Net-(EDBG-DMF_S)") (class "Default")
      (node (ref "EDBG") (pin "B9") (pinfunction "DMF_S_B9") (pintype "bidirectional"))
      (node (ref "R315") (pin "2") (pinfunction "2_2") (pintype "passive"))
    )
    (net (code "33") (name "Net-(EDBG-DPF_S)") (class "Default")
      (node (ref "EDBG") (pin "B8") (pinfunction "DPF_S_B8") (pintype "bidirectional"))
      (node (ref "R316") (pin "2") (pinfunction "2_2") (pintype "passive"))
    )
    (net (code "34") (name "Net-(EDBG-PA03)") (class "Default")
      (node (ref "EDBG") (pin "F9") (pinfunction "PA03_F9") (pintype "bidirectional"))
      (node (ref "R305") (pin "2") (pinfunction "2_2") (pintype "passive"))
    )
    (net (code "35") (name "Net-(EDBG-PA04)") (class "Default")
      (node (ref "EDBG") (pin "E9") (pinfunction "PA04_E9") (pintype "bidirectional"))
      (node (ref "R306") (pin "2") (pinfunction "2_2") (pintype "passive"))
    )
    (net (code "36") (name "Net-(EDBG-PA08)") (class "Default")
      (node (ref "EDBG") (pin "F8") (pinfunction "PA08_F8") (pintype "bidirectional"))
      (node (ref "R307") (pin "2") (pinfunction "2_2") (pintype "passive"))
    )
    (net (code "37") (name "Net-(EDBG-PA09)") (class "Default")
      (node (ref "EDBG") (pin "D8") (pinfunction "PA09_D8") (pintype "bidirectional"))
      (node (ref "R308") (pin "2") (pinfunction "2_2") (pintype "passive"))
    )
    (net (code "38") (name "Net-(EDBG-PA10)") (class "Default")
      (node (ref "EDBG") (pin "C10") (pinfunction "PA10_C10") (pintype "bidirectional"))
      (node (ref "R309") (pin "2") (pinfunction "2_2") (pintype "passive"))
    )
    (net (code "39") (name "Net-(EDBG-PA11)") (class "Default")
      (node (ref "EDBG") (pin "C9") (pinfunction "PA11_C9") (pintype "bidirectional"))
      (node (ref "R310") (pin "2") (pinfunction "2_2") (pintype "passive"))
    )
    (net (code "40") (name "Net-(EDBG-PC02)") (class "Default")
      (node (ref "C300") (pin "1") (pinfunction "1_1") (pintype "passive"))
      (node (ref "EDBG") (pin "A5") (pinfunction "PC02_A5") (pintype "bidirectional"))
      (node (ref "X300") (pin "3") (pinfunction "C2_3") (pintype "passive"))
    )
    (net (code "41") (name "Net-(EDBG-PC03)") (class "Default")
      (node (ref "C301") (pin "1") (pinfunction "1_1") (pintype "passive"))
      (node (ref "EDBG") (pin "A6") (pinfunction "PC03_A6") (pintype "bidirectional"))
      (node (ref "X300") (pin "1") (pinfunction "C1_1") (pintype "passive"))
    )
    (net (code "42") (name "Net-(EDBG-PX27)") (class "Default")
      (node (ref "EDBG") (pin "K2") (pinfunction "PX27_K2") (pintype "bidirectional"))
      (node (ref "R311") (pin "1") (pinfunction "1_1") (pintype "passive"))
    )
    (net (code "43") (name "Net-(EDBG-PX28)") (class "Default")
      (node (ref "EDBG") (pin "K3") (pinfunction "PX28_K3") (pintype "bidirectional"))
      (node (ref "R312") (pin "1") (pinfunction "1_1") (pintype "passive"))
    )
    (net (code "44") (name "Net-(EDBG-PX29)") (class "Default")
      (node (ref "EDBG") (pin "J4") (pinfunction "PX29_J4") (pintype "bidirectional"))
      (node (ref "R313") (pin "1") (pinfunction "1_1") (pintype "passive"))
    )
    (net (code "45") (name "Net-(EDBG-PX30)") (class "Default")
      (node (ref "EDBG") (pin "G5") (pinfunction "PX30_G5") (pintype "bidirectional"))
      (node (ref "R314") (pin "1") (pinfunction "1_1") (pintype "passive"))
    )
    (net (code "46") (name "Net-(EDBG-USB_VBIAS)") (class "Default")
      (node (ref "C302") (pin "1") (pinfunction "1_1") (pintype "passive"))
      (node (ref "EDBG") (pin "C7") (pinfunction "USB_VBIAS_C7") (pintype "bidirectional"))
      (node (ref "R317") (pin "2") (pinfunction "2_2") (pintype "passive"))
    )
    (net (code "47") (name "Net-(EDBG-VDDANA)") (class "Default")
      (node (ref "C304") (pin "1") (pinfunction "1_1") (pintype "passive"))
      (node (ref "EDBG") (pin "J6") (pinfunction "VDDANA_J6") (pintype "bidirectional"))
      (node (ref "L301") (pin "2") (pinfunction "2_2") (pintype "passive"))
    )
    (net (code "48") (name "Net-(EDBG-VDDCORE)") (class "Default")
      (node (ref "C305") (pin "1") (pinfunction "1_1") (pintype "passive"))
      (node (ref "C306") (pin "1") (pinfunction "1_1") (pintype "passive"))
      (node (ref "EDBG") (pin "E10") (pinfunction "VDDCORE_E10") (pintype "bidirectional"))
    )
    (net (code "49") (name "Net-(IC2-VDDANA)") (class "Default")
      (node (ref "C106") (pin "1") (pinfunction "1_1") (pintype "passive"))
      (node (ref "C107") (pin "1") (pinfunction "1_1") (pintype "passive"))
      (node (ref "IC2") (pin "6") (pinfunction "VDDANA_6") (pintype "power_in"))
      (node (ref "L100") (pin "1") (pinfunction "1_1") (pintype "passive"))
    )
    (net (code "50") (name "Net-(J107-VUSB)") (class "Default")
      (node (ref "C110") (pin "2") (pinfunction "2_2") (pintype "passive"))
      (node (ref "D103") (pin "4") (pinfunction "4_4") (pintype "bidirectional"))
      (node (ref "J107") (pin "VBUS") (pinfunction "VUSB_VBUS") (pintype "bidirectional"))
      (node (ref "L101") (pin "1") (pinfunction "1_1") (pintype "passive"))
    )
    (net (code "51") (name "Net-(LED3-PadA)") (class "Default")
      (node (ref "LED3") (pin "A") (pinfunction "A_A") (pintype "passive"))
      (node (ref "R106") (pin "2") (pinfunction "2_2") (pintype "passive"))
    )
    (net (code "52") (name "Net-(Q201-S)") (class "Default")
      (node (ref "Q201") (pin "2") (pinfunction "S_2") (pintype "passive"))
      (node (ref "R207") (pin "1") (pinfunction "1_1") (pintype "passive"))
      (node (ref "R208") (pin "1") (pinfunction "1_1") (pintype "passive"))
    )
    (net (code "53") (name "Net-(Q202-G)") (class "Default")
      (node (ref "Q202") (pin "1") (pinfunction "G_1") (pintype "passive"))
      (node (ref "Q203") (pin "2") (pinfunction "S_2") (pintype "passive"))
      (node (ref "R209") (pin "1") (pinfunction "1_1") (pintype "passive"))
    )
    (net (code "54") (name "Net-(Q300A-D)") (class "Default")
      (node (ref "D301") (pin "C") (pinfunction "C_C") (pintype "passive"))
      (node (ref "Q300") (pin "3") (pinfunction "D_3") (pintype "passive"))
    )
    (net (code "55") (name "Net-(Q300B-D)") (class "Default")
      (node (ref "D300") (pin "C") (pinfunction "C_C") (pintype "passive"))
      (node (ref "Q300") (pin "6") (pinfunction "D_6") (pintype "passive"))
      (node (ref "R303") (pin "2") (pinfunction "2_2") (pintype "passive"))
    )
    (net (code "56") (name "Net-(R102-Pad1)") (class "Default")
      (node (ref "R102") (pin "1") (pinfunction "1_1") (pintype "passive"))
      (node (ref "S100") (pin "3") (pinfunction "3_3") (pintype "passive"))
      (node (ref "S100") (pin "4") (pinfunction "4_4") (pintype "passive"))
    )
    (net (code "57") (name "Net-(TR3-D)") (class "Default")
      (node (ref "LED3") (pin "C") (pinfunction "C_C") (pintype "passive"))
      (node (ref "TR3") (pin "1") (pinfunction "D_1") (pintype "passive"))
    )
    (net (code "58") (name "PA00_XIN32") (class "Default")
      (node (ref "C103") (pin "2") (pinfunction "2_2") (pintype "passive"))
      (node (ref "IC2") (pin "1") (pinfunction "PA0/XIN32/EIC/SCOM1PAD0/TC2_1") (pintype "bidirectional"))
      (node (ref "XC100") (pin "2") (pinfunction "2_2") (pintype "passive"))
    )
    (net (code "59") (name "PA01_XOUT32") (class "Default")
      (node (ref "C104") (pin "2") (pinfunction "2_2") (pintype "passive"))
      (node (ref "IC2") (pin "2") (pinfunction "PA1/XOUT32/EIC/SCOM1PAD1/TC2_2") (pintype "bidirectional"))
      (node (ref "J103") (pin "1") (pinfunction "1_1") (pintype "passive"))
      (node (ref "J103") (pin "2") (pinfunction "2_2") (pintype "passive"))
      (node (ref "XC100") (pin "1") (pinfunction "1_1") (pintype "passive"))
    )
    (net (code "60") (name "PA02_AIN0") (class "Default")
      (node (ref "IC2") (pin "3") (pinfunction "PA2/EIC/AIN0_3") (pintype "bidirectional"))
      (node (ref "J106") (pin "1") (pinfunction "1_1") (pintype "passive"))
    )
    (net (code "61") (name "PA03_AREFA") (class "Default")
      (node (ref "C112") (pin "1") (pinfunction "1_1") (pintype "passive"))
      (node (ref "C113") (pin "1") (pinfunction "1_1") (pintype "passive"))
      (node (ref "IC2") (pin "4") (pinfunction "PA3/EIC/REF/AIN1_4") (pintype "bidirectional"))
      (node (ref "J101") (pin "8") (pinfunction "8_8") (pintype "passive"))
    )
    (net (code "62") (name "PA04_AIN4") (class "Default")
      (node (ref "IC2") (pin "9") (pinfunction "PA4/EIC/REF/AIN4/SCOM0PAD0/TC0_9") (pintype "bidirectional"))
      (node (ref "J106") (pin "4") (pinfunction "4_4") (pintype "passive"))
    )
    (net (code "63") (name "PA05_AIN5") (class "Default")
      (node (ref "IC2") (pin "10") (pinfunction "PA5/EIC/AIN5/SCOM0PAD1/TC0_10") (pintype "bidirectional"))
      (node (ref "J106") (pin "5") (pinfunction "5_5") (pintype "passive"))
    )
    (net (code "64") (name "PA08_TCC0-W0") (class "Default")
      (node (ref "IC2") (pin "23") (pinfunction "PA14/XIN/EIC/SCOM2PAD2+/TC3_23") (pintype "bidirectional"))
      (node (ref "J102") (pin "5") (pinfunction "5_5") (pintype "passive"))
    )
    (net (code "65") (name "PA09_TCC0-W1") (class "Default")
      (node (ref "IC2") (pin "14") (pinfunction "PA9/I2C/EIC/AIN17/SCOM2PAD1+/TC0_14") (pintype "bidirectional"))
      (node (ref "J102") (pin "4") (pinfunction "4_4") (pintype "passive"))
    )
    (net (code "66") (name "PA10_TCC0-W2") (class "Default")
      (node (ref "IC2") (pin "15") (pinfunction "PA10/EIC/AIN18/SCOM2PAD2+/TC1_15") (pintype "bidirectional"))
      (node (ref "J102") (pin "2") (pinfunction "2_2") (pintype "passive"))
    )
    (net (code "67") (name "PA11_TCC0-W3") (class "Default")
      (node (ref "IC2") (pin "16") (pinfunction "PA11/EIC/AIN19/SCOM2PAD3+/TC1_16") (pintype "bidirectional"))
      (node (ref "J102") (pin "1") (pinfunction "1_1") (pintype "passive"))
    )
    (net (code "68") (name "PA13_GPIO") (class "Default")
      (node (ref "IC2") (pin "22") (pinfunction "PA13/I2C/EIC/SCOM2PAD1+/TC2_22") (pintype "bidirectional"))
    )
    (net (code "69") (name "PA14_TCC0-W4") (class "Default")
      (node (ref "IC2") (pin "13") (pinfunction "PA8/I2C/AIN16/SCOM2PAD0+/TC0_13") (pintype "bidirectional"))
      (node (ref "J102") (pin "3") (pinfunction "3_3") (pintype "passive"))
    )
    (net (code "70") (name "PA15_TCC0-W5") (class "Default")
      (node (ref "IC2") (pin "24") (pinfunction "PA15/XOUT/EIC/SCOM2PAD3+/TC3_24") (pintype "bidirectional"))
      (node (ref "J102") (pin "6") (pinfunction "6_6") (pintype "passive"))
    )
    (net (code "71") (name "PA20_TCC0-W6") (class "Default")
      (node (ref "IC2") (pin "29") (pinfunction "PA20/EIC/SCOM5PAD2+_29") (pintype "bidirectional"))
      (node (ref "J102") (pin "7") (pinfunction "7_7") (pintype "passive"))
    )
    (net (code "72") (name "PA27_TX_LED") (class "Default")
      (node (ref "D102") (pin "C") (pinfunction "C_C") (pintype "passive"))
      (node (ref "IC2") (pin "39") (pinfunction "PA27/EIC_39") (pintype "bidirectional"))
    )
    (net (code "73") (name "PA28_USB_HOST_EN") (class "Default")
      (node (ref "IC2") (pin "41") (pinfunction "PA28/EIC_41") (pintype "bidirectional"))
      (node (ref "R113") (pin "2") (pinfunction "2_2") (pintype "passive"))
    )
    (net (code "74") (name "PA30_SWCLK") (class "Default")
      (node (ref "IC2") (pin "45") (pinfunction "PA30/EIC/SCOM1PAD2/TC1_45") (pintype "bidirectional"))
      (node (ref "R104") (pin "1") (pinfunction "1_1") (pintype "passive"))
    )
    (net (code "75") (name "PA31_SWDIO") (class "Default")
      (node (ref "IC2") (pin "46") (pinfunction "PA31/EIC/SCOM1PAD3/TC1_46") (pintype "bidirectional"))
      (node (ref "R105") (pin "2") (pinfunction "2_2") (pintype "passive"))
    )
    (net (code "76") (name "PB02_AIN10") (class "Default")
      (node (ref "IC2") (pin "47") (pinfunction "PB2/EIC/AIN10/SCOM5PAD0_47") (pintype "bidirectional"))
      (node (ref "J106") (pin "6") (pinfunction "6_6") (pintype "passive"))
    )
    (net (code "77") (name "PB03_RX_LED") (class "Default")
      (node (ref "D101") (pin "C") (pinfunction "C_C") (pintype "passive"))
      (node (ref "IC2") (pin "48") (pinfunction "PB3/EIC/AIN11/SCOM5PAD1_48") (pintype "bidirectional"))
    )
    (net (code "78") (name "PB08_AIN2") (class "Default")
      (node (ref "IC2") (pin "7") (pinfunction "PB8/EIC/AIN2/SCOM4PAD0/TC4_7") (pintype "bidirectional"))
      (node (ref "J106") (pin "2") (pinfunction "2_2") (pintype "passive"))
    )
    (net (code "79") (name "PB09_AIN3") (class "Default")
      (node (ref "IC2") (pin "8") (pinfunction "PB9/EIC/AIN3/SCOM4PAD1//TC4_8") (pintype "bidirectional"))
      (node (ref "J106") (pin "3") (pinfunction "3_3") (pintype "passive"))
    )
    (net (code "80") (name "PB10_S4_SPI_MOSI") (class "Default")
      (node (ref "IC2") (pin "19") (pinfunction "PB10/EIC/SCOM4PAD2/TC5_19") (pintype "bidirectional"))
      (node (ref "ICSP") (pin "4") (pinfunction "4_4") (pintype "passive"))
    )
    (net (code "81") (name "PB11_S4_SPI_SCK") (class "Default")
      (node (ref "IC2") (pin "20") (pinfunction "PB11/EIC/SCOM4PAD3/TC5_20") (pintype "bidirectional"))
      (node (ref "ICSP") (pin "3") (pinfunction "3_3") (pintype "passive"))
    )
    (net (code "82") (name "PB12_S4_SPI_MISO") (class "Default")
      (node (ref "IC2") (pin "21") (pinfunction "PA12/I2C/EIC/SCOM2PAD0+/TC2_21") (pintype "bidirectional"))
      (node (ref "ICSP") (pin "1") (pinfunction "1_1") (pintype "passive"))
    )
    (net (code "83") (name "POWER_LED_CTRL") (class "Default")
      (node (ref "EDBG") (pin "K4") (pinfunction "PX32/PX15_K4") (pintype "bidirectional"))
      (node (ref "Q300") (pin "2") (pinfunction "G_2") (pintype "passive"))
      (node (ref "R300") (pin "1") (pinfunction "1_1") (pintype "passive"))
    )
    (net (code "84") (name "RXD") (class "Default")
      (node (ref "IC2") (pin "38") (pinfunction "PB23/EIC/SCOM5PAD3_38") (pintype "bidirectional"))
      (node (ref "R306") (pin "1") (pinfunction "1_1") (pintype "passive"))
    )
    (net (code "85") (name "SAMD21_RESET") (class "Default")
      (node (ref "EDBG") (pin "B4") (pinfunction "PA29_B4") (pintype "bidirectional"))
      (node (ref "IC2") (pin "40") (pinfunction "RESETN_40") (pintype "bidirectional"))
      (node (ref "R103") (pin "1") (pinfunction "1_1") (pintype "passive"))
    )
    (net (code "86") (name "SCK") (class "Default")
      (node (ref "IC2") (pin "26") (pinfunction "PA17/I2C/EIC/SCOM1PAD1+/TC2_26") (pintype "bidirectional"))
      (node (ref "J101") (pin "6") (pinfunction "6_6") (pintype "passive"))
      (node (ref "R109") (pin "1") (pinfunction "1_1") (pintype "passive"))
      (node (ref "R313") (pin "2") (pinfunction "2_2") (pintype "passive"))
      (node (ref "TR3") (pin "3") (pinfunction "G_3") (pintype "passive"))
    )
    (net (code "87") (name "SCL") (class "Default")
      (node (ref "EDBG") (pin "F7") (pinfunction "PA26/PB05_F7") (pintype "bidirectional"))
      (node (ref "IC2") (pin "32") (pinfunction "PA23/I2C/EIC/SCOM5PAD1+/TC4_32") (pintype "bidirectional"))
      (node (ref "J101") (pin "10") (pinfunction "10_10") (pintype "passive"))
      (node (ref "R112") (pin "1") (pinfunction "1_1") (pintype "passive"))
    )
    (net (code "88") (name "SDA") (class "Default")
      (node (ref "EDBG") (pin "G7") (pinfunction "PA12/PA25_G7") (pintype "bidirectional"))
      (node (ref "IC2") (pin "31") (pinfunction "PA22/I2C/EIC/SCOM5PAD0+/TC4_31") (pintype "bidirectional"))
      (node (ref "J101") (pin "9") (pinfunction "9_9") (pintype "passive"))
      (node (ref "R111") (pin "1") (pinfunction "1_1") (pintype "passive"))
    )
    (net (code "89") (name "SS") (class "Default")
      (node (ref "IC2") (pin "27") (pinfunction "PA18/EIC/SCOM1PAD2+/TC3_27") (pintype "bidirectional"))
      (node (ref "J101") (pin "3") (pinfunction "3_3") (pintype "passive"))
      (node (ref "R314") (pin "2") (pinfunction "2_2") (pintype "passive"))
    )
    (net (code "90") (name "STATUS_LED_CTRL") (class "Default")
      (node (ref "EDBG") (pin "F1") (pinfunction "PX59/PX19_F1") (pintype "bidirectional"))
      (node (ref "Q300") (pin "5") (pinfunction "G_5") (pintype "passive"))
      (node (ref "R304") (pin "2") (pinfunction "2_2") (pintype "passive"))
    )
    (net (code "91") (name "SW") (class "Default")
      (node (ref "C200") (pin "2") (pinfunction "2_2") (pintype "passive"))
      (node (ref "D202") (pin "P$1") (pinfunction "K_P$1") (pintype "bidirectional"))
      (node (ref "L201") (pin "P$1") (pinfunction "1_P$1") (pintype "passive"))
      (node (ref "U200") (pin "6") (pinfunction "SW_6") (pintype "output"))
    )
    (net (code "92") (name "SWCLK") (class "Default")
      (node (ref "EDBG") (pin "D6") (pinfunction "PB07_D6") (pintype "bidirectional"))
      (node (ref "J100") (pin "4") (pinfunction "4_4") (pintype "passive"))
      (node (ref "R104") (pin "2") (pinfunction "2_2") (pintype "passive"))
    )
    (net (code "93") (name "SWDIO") (class "Default")
      (node (ref "EDBG") (pin "C5") (pinfunction "PB09_C5") (pintype "bidirectional"))
      (node (ref "J100") (pin "2") (pinfunction "2_2") (pintype "passive"))
      (node (ref "R105") (pin "1") (pinfunction "1_1") (pintype "passive"))
    )
    (net (code "94") (name "TARGET_RESET") (class "Default")
      (node (ref "C101") (pin "1") (pinfunction "1_1") (pintype "passive"))
      (node (ref "ICSP") (pin "5") (pinfunction "5_5") (pintype "passive"))
      (node (ref "J100") (pin "10") (pinfunction "10_10") (pintype "passive"))
      (node (ref "J105") (pin "3") (pinfunction "3_3") (pintype "passive"))
      (node (ref "R100") (pin "1") (pinfunction "1_1") (pintype "passive"))
      (node (ref "R101") (pin "2") (pinfunction "2_2") (pintype "passive"))
      (node (ref "R102") (pin "2") (pinfunction "2_2") (pintype "passive"))
      (node (ref "R103") (pin "2") (pinfunction "2_2") (pintype "passive"))
    )
    (net (code "95") (name "TARGET_RESET_SENSE") (class "Default")
      (node (ref "EDBG") (pin "H2") (pinfunction "PX21_H2") (pintype "bidirectional"))
      (node (ref "R101") (pin "1") (pinfunction "1_1") (pintype "passive"))
    )
    (net (code "96") (name "TARGET_USB_N") (class "Default")
      (node (ref "D103") (pin "3") (pinfunction "3_3") (pintype "bidirectional"))
      (node (ref "IC2") (pin "33") (pinfunction "PA24/EIC/SCOM3PAD2+/TC5_33") (pintype "bidirectional"))
      (node (ref "J107") (pin "D-") (pinfunction "D-_D-") (pintype "bidirectional"))
    )
    (net (code "97") (name "TARGET_USB_P") (class "Default")
      (node (ref "D103") (pin "2") (pinfunction "2_2") (pintype "bidirectional"))
      (node (ref "IC2") (pin "34") (pinfunction "PA25/EIC/SCOM3PAD3+/TC5_34") (pintype "bidirectional"))
      (node (ref "J107") (pin "D+") (pinfunction "D+_D+") (pintype "bidirectional"))
    )
    (net (code "98") (name "TXD") (class "Default")
      (node (ref "IC2") (pin "37") (pinfunction "PB22/EIC/SCOM5PAD2_37") (pintype "bidirectional"))
      (node (ref "R305") (pin "1") (pinfunction "1_1") (pintype "passive"))
    )
    (net (code "99") (name "USB_HOST_ENABLE") (class "Default")
      (node (ref "J107") (pin "ID") (pinfunction "ID_ID") (pintype "bidirectional"))
      (node (ref "Q203") (pin "1") (pinfunction "G_1") (pintype "passive"))
      (node (ref "R113") (pin "1") (pinfunction "1_1") (pintype "passive"))
      (node (ref "R210") (pin "2") (pinfunction "2_2") (pintype "passive"))
    )
    (net (code "100") (name "VCC_EDBG_3V3") (class "Default")
      (node (ref "C309") (pin "1") (pinfunction "1_1") (pintype "passive"))
      (node (ref "C310") (pin "1") (pinfunction "1_1") (pintype "passive"))
      (node (ref "C311") (pin "1") (pinfunction "1_1") (pintype "passive"))
      (node (ref "C312") (pin "1") (pinfunction "1_1") (pintype "passive"))
      (node (ref "C313") (pin "1") (pinfunction "1_1") (pintype "passive"))
      (node (ref "C314") (pin "1") (pinfunction "1_1") (pintype "passive"))
      (node (ref "C315") (pin "1") (pinfunction "1_1") (pintype "passive"))
      (node (ref "EDBG") (pin "B5") (pinfunction "VDDIO_B5") (pintype "bidirectional"))
      (node (ref "EDBG") (pin "B6") (pinfunction "VDDIO1_B6") (pintype "bidirectional"))
      (node (ref "EDBG") (pin "D10") (pinfunction "VDDIN1_D10") (pintype "bidirectional"))
      (node (ref "EDBG") (pin "D9") (pinfunction "VDDIN_D9") (pintype "bidirectional"))
      (node (ref "EDBG") (pin "E5") (pinfunction "VDDIO2_E5") (pintype "bidirectional"))
      (node (ref "EDBG") (pin "F2") (pinfunction "VDDIO3_F2") (pintype "bidirectional"))
      (node (ref "EDBG") (pin "F6") (pinfunction "VDDIO4_F6") (pintype "bidirectional"))
      (node (ref "EDBG") (pin "J5") (pinfunction "VDDIO5_J5") (pintype "bidirectional"))
      (node (ref "J301") (pin "4") (pinfunction "4_4") (pintype "passive"))
      (node (ref "L301") (pin "1") (pinfunction "1_1") (pintype "passive"))
      (node (ref "R300") (pin "2") (pinfunction "2_2") (pintype "passive"))
      (node (ref "R301") (pin "2") (pinfunction "2_2") (pintype "passive"))
      (node (ref "R302") (pin "2") (pinfunction "2_2") (pintype "passive"))
      (node (ref "R319") (pin "2") (pinfunction "2_2") (pintype "passive"))
    )
    (net (code "101") (name "VCC_EDBG_USB") (class "Default")
      (node (ref "EDBG") (pin "A10") (pinfunction "USB_VBUS_A10") (pintype "bidirectional"))
      (node (ref "F300") (pin "2") (pinfunction "2_2") (pintype "passive"))
      (node (ref "Q200") (pin "3") (pinfunction "D_3") (pintype "passive"))
      (node (ref "Q201") (pin "1") (pinfunction "D_1") (pintype "passive"))
      (node (ref "R208") (pin "2") (pinfunction "2_2") (pintype "passive"))
    )
    (net (code "102") (name "VCC_EXT_VIN") (class "Default")
      (node (ref "C203") (pin "+") (pinfunction "+_+") (pintype "passive"))
      (node (ref "J105") (pin "8") (pinfunction "8_8") (pintype "passive"))
      (node (ref "L200") (pin "2") (pinfunction "2_2") (pintype "passive"))
      (node (ref "R200") (pin "1") (pinfunction "1_1") (pintype "passive"))
      (node (ref "U200") (pin "5") (pinfunction "VIN_5") (pintype "input"))
    )
    (net (code "103") (name "VDDCORE") (class "Default")
      (node (ref "C102") (pin "1") (pinfunction "1_1") (pintype "passive"))
      (node (ref "IC2") (pin "43") (pinfunction "VDDCORE1_43") (pintype "input"))
    )
    (net (code "104") (name "VEXT") (class "Default")
      (node (ref "D201") (pin "A") (pinfunction "A_A") (pintype "passive"))
      (node (ref "J200") (pin "2") (pinfunction "2_2") (pintype "power_in"))
      (node (ref "R205") (pin "2") (pinfunction "2_2") (pintype "passive"))
    )
    (net (code "105") (name "VIN_DETECT") (class "Default")
      (node (ref "Q200") (pin "1") (pinfunction "G_1") (pintype "passive"))
      (node (ref "R205") (pin "1") (pinfunction "1_1") (pintype "passive"))
      (node (ref "R206") (pin "2") (pinfunction "2_2") (pintype "passive"))
    )
    (net (code "106") (name "XVCC") (class "Default")
      (node (ref "C307") (pin "1") (pinfunction "1_1") (pintype "passive"))
      (node (ref "D302") (pin "4") (pinfunction "4_4") (pintype "bidirectional"))
      (node (ref "J300") (pin "VBUS") (pinfunction "VUSB_VBUS") (pintype "bidirectional"))
      (node (ref "L300") (pin "1") (pinfunction "1_1") (pintype "passive"))
    )
    (net (code "107") (name "unconnected-(EDBG-PA00{slash}PA18-PadG8)") (class "Default")
      (node (ref "EDBG") (pin "G8") (pinfunction "PA00/PA18_G8") (pintype "bidirectional"))
    )
    (net (code "108") (name "unconnected-(EDBG-PA01{slash}PA17-PadG10)") (class "Default")
      (node (ref "EDBG") (pin "G10") (pinfunction "PA01/PA17_G10") (pintype "bidirectional"))
    )
    (net (code "109") (name "unconnected-(EDBG-PA02{slash}PX47-PadE1)") (class "Default")
      (node (ref "EDBG") (pin "E1") (pinfunction "PA02/PX47_E1") (pintype "bidirectional"))
    )
    (net (code "110") (name "unconnected-(EDBG-PA05-PadG9)") (class "Default")
      (node (ref "EDBG") (pin "G9") (pinfunction "PA05_G9") (pintype "bidirectional"))
    )
    (net (code "111") (name "unconnected-(EDBG-PA06{slash}PA13-PadE8)") (class "Default")
      (node (ref "EDBG") (pin "E8") (pinfunction "PA06/PA13_E8") (pintype "bidirectional"))
    )
    (net (code "112") (name "unconnected-(EDBG-PA07{slash}PA19-PadH10)") (class "Default")
      (node (ref "EDBG") (pin "H10") (pinfunction "PA07/PA19_H10") (pintype "bidirectional"))
    )
    (net (code "113") (name "unconnected-(EDBG-PA14{slash}PX11-PadK7)") (class "Default")
      (node (ref "EDBG") (pin "K7") (pinfunction "PA14/PX11_K7") (pintype "bidirectional"))
    )
    (net (code "114") (name "unconnected-(EDBG-PA15{slash}PX45-PadJ7)") (class "Default")
      (node (ref "EDBG") (pin "J7") (pinfunction "PA15/PX45_J7") (pintype "bidirectional"))
    )
    (net (code "115") (name "unconnected-(EDBG-PA16-PadE7)") (class "Default")
      (node (ref "EDBG") (pin "E7") (pinfunction "PA16_E7") (pintype "bidirectional"))
    )
    (net (code "116") (name "unconnected-(EDBG-PA22{slash}PX20-PadH6)") (class "Default")
      (node (ref "EDBG") (pin "H6") (pinfunction "PA22/PX20_H6") (pintype "bidirectional"))
    )
    (net (code "117") (name "unconnected-(EDBG-PA23{slash}PX46-PadG6)") (class "Default")
      (node (ref "EDBG") (pin "G6") (pinfunction "PA23/PX46_G6") (pintype "bidirectional"))
    )
    (net (code "118") (name "unconnected-(EDBG-PA24{slash}PX17-PadJ10)") (class "Default")
      (node (ref "EDBG") (pin "J10") (pinfunction "PA24/PX17_J10") (pintype "bidirectional"))
    )
    (net (code "119") (name "unconnected-(EDBG-PA27-PadA2)") (class "Default")
      (node (ref "EDBG") (pin "A2") (pinfunction "PA27_A2") (pintype "bidirectional"))
    )
    (net (code "120") (name "unconnected-(EDBG-PA28-PadA1)") (class "Default")
      (node (ref "EDBG") (pin "A1") (pinfunction "PA28_A1") (pintype "bidirectional"))
    )
    (net (code "121") (name "unconnected-(EDBG-PA30-PadA4)") (class "Default")
      (node (ref "EDBG") (pin "A4") (pinfunction "PA30_A4") (pintype "bidirectional"))
    )
    (net (code "122") (name "unconnected-(EDBG-PA31-PadC2)") (class "Default")
      (node (ref "EDBG") (pin "C2") (pinfunction "PA31_C2") (pintype "bidirectional"))
    )
    (net (code "123") (name "unconnected-(EDBG-PB00-PadB1)") (class "Default")
      (node (ref "EDBG") (pin "B1") (pinfunction "PB00_B1") (pintype "bidirectional"))
    )
    (net (code "124") (name "unconnected-(EDBG-PB01-PadB2)") (class "Default")
      (node (ref "EDBG") (pin "B2") (pinfunction "PB01_B2") (pintype "bidirectional"))
    )
    (net (code "125") (name "unconnected-(EDBG-PB02-PadB3)") (class "Default")
      (node (ref "EDBG") (pin "B3") (pinfunction "PB02_B3") (pintype "bidirectional"))
    )
    (net (code "126") (name "unconnected-(EDBG-PB03-PadC4)") (class "Default")
      (node (ref "EDBG") (pin "C4") (pinfunction "PB03_C4") (pintype "bidirectional"))
    )
    (net (code "127") (name "unconnected-(EDBG-PB04-PadA3)") (class "Default")
      (node (ref "EDBG") (pin "A3") (pinfunction "PB04_A3") (pintype "bidirectional"))
    )
    (net (code "128") (name "unconnected-(EDBG-PB06-PadD7)") (class "Default")
      (node (ref "EDBG") (pin "D7") (pinfunction "PB06_D7") (pintype "bidirectional"))
    )
    (net (code "129") (name "unconnected-(EDBG-PB08-PadC6)") (class "Default")
      (node (ref "EDBG") (pin "C6") (pinfunction "PB08_C6") (pintype "bidirectional"))
    )
    (net (code "130") (name "unconnected-(EDBG-PB10-PadD5)") (class "Default")
      (node (ref "EDBG") (pin "D5") (pinfunction "PB10_D5") (pintype "bidirectional"))
    )
    (net (code "131") (name "unconnected-(EDBG-PB11-PadC1)") (class "Default")
      (node (ref "EDBG") (pin "C1") (pinfunction "PB11_C1") (pintype "bidirectional"))
    )
    (net (code "132") (name "unconnected-(EDBG-PC00{slash}PX14-PadK5)") (class "Default")
      (node (ref "EDBG") (pin "K5") (pinfunction "PC00/PX14_K5") (pintype "bidirectional"))
    )
    (net (code "133") (name "unconnected-(EDBG-PC01-PadK6)") (class "Default")
      (node (ref "EDBG") (pin "K6") (pinfunction "PC01_K6") (pintype "bidirectional"))
    )
    (net (code "134") (name "unconnected-(EDBG-PC04-PadB7)") (class "Default")
      (node (ref "EDBG") (pin "B7") (pinfunction "PC04_B7") (pintype "bidirectional"))
    )
    (net (code "135") (name "unconnected-(EDBG-PC05-PadA7)") (class "Default")
      (node (ref "EDBG") (pin "A7") (pinfunction "PC05_A7") (pintype "bidirectional"))
    )
    (net (code "136") (name "unconnected-(EDBG-PX00-PadG4)") (class "Default")
      (node (ref "EDBG") (pin "G4") (pinfunction "PX00_G4") (pintype "bidirectional"))
    )
    (net (code "137") (name "unconnected-(EDBG-PX01-PadG2)") (class "Default")
      (node (ref "EDBG") (pin "G2") (pinfunction "PX01_G2") (pintype "bidirectional"))
    )
    (net (code "138") (name "unconnected-(EDBG-PX02-PadG3)") (class "Default")
      (node (ref "EDBG") (pin "G3") (pinfunction "PX02_G3") (pintype "bidirectional"))
    )
    (net (code "139") (name "unconnected-(EDBG-PX03-PadJ1)") (class "Default")
      (node (ref "EDBG") (pin "J1") (pinfunction "PX03_J1") (pintype "bidirectional"))
    )
    (net (code "140") (name "unconnected-(EDBG-PX04-PadH1)") (class "Default")
      (node (ref "EDBG") (pin "H1") (pinfunction "PX04_H1") (pintype "bidirectional"))
    )
    (net (code "141") (name "unconnected-(EDBG-PX05-PadG1)") (class "Default")
      (node (ref "EDBG") (pin "G1") (pinfunction "PX05_G1") (pintype "bidirectional"))
    )
    (net (code "142") (name "unconnected-(EDBG-PX06-PadF3)") (class "Default")
      (node (ref "EDBG") (pin "F3") (pinfunction "PX06_F3") (pintype "bidirectional"))
    )
    (net (code "143") (name "unconnected-(EDBG-PX07-PadF4)") (class "Default")
      (node (ref "EDBG") (pin "F4") (pinfunction "PX07_F4") (pintype "bidirectional"))
    )
    (net (code "144") (name "unconnected-(EDBG-PX08-PadE3)") (class "Default")
      (node (ref "EDBG") (pin "E3") (pinfunction "PX08_E3") (pintype "bidirectional"))
    )
    (net (code "145") (name "unconnected-(EDBG-PX09-PadE4)") (class "Default")
      (node (ref "EDBG") (pin "E4") (pinfunction "PX09_E4") (pintype "bidirectional"))
    )
    (net (code "146") (name "unconnected-(EDBG-PX10-PadD2)") (class "Default")
      (node (ref "EDBG") (pin "D2") (pinfunction "PX10_D2") (pintype "bidirectional"))
    )
    (net (code "147") (name "unconnected-(EDBG-PX12-PadD1)") (class "Default")
      (node (ref "EDBG") (pin "D1") (pinfunction "PX12_D1") (pintype "bidirectional"))
    )
    (net (code "148") (name "unconnected-(EDBG-PX13-PadD3)") (class "Default")
      (node (ref "EDBG") (pin "D3") (pinfunction "PX13_D3") (pintype "bidirectional"))
    )
    (net (code "149") (name "unconnected-(EDBG-PX23-PadK1)") (class "Default")
      (node (ref "EDBG") (pin "K1") (pinfunction "PX23_K1") (pintype "bidirectional"))
    )
    (net (code "150") (name "unconnected-(EDBG-PX24-PadJ2)") (class "Default")
      (node (ref "EDBG") (pin "J2") (pinfunction "PX24_J2") (pintype "bidirectional"))
    )
    (net (code "151") (name "unconnected-(EDBG-PX25-PadH4)") (class "Default")
      (node (ref "EDBG") (pin "H4") (pinfunction "PX25_H4") (pintype "bidirectional"))
    )
    (net (code "152") (name "unconnected-(EDBG-PX26-PadJ3)") (class "Default")
      (node (ref "EDBG") (pin "J3") (pinfunction "PX26_J3") (pintype "bidirectional"))
    )
    (net (code "153") (name "unconnected-(EDBG-PX31-PadH5)") (class "Default")
      (node (ref "EDBG") (pin "H5") (pinfunction "PX31_H5") (pintype "bidirectional"))
    )
    (net (code "154") (name "unconnected-(EDBG-PX53{slash}PX16-PadD4)") (class "Default")
      (node (ref "EDBG") (pin "D4") (pinfunction "PX53/PX16_D4") (pintype "bidirectional"))
    )
    (net (code "155") (name "unconnected-(J100-Pad6)") (class "Default")
      (node (ref "J100") (pin "6") (pinfunction "6_6") (pintype "passive"))
    )
    (net (code "156") (name "unconnected-(J100-Pad7)") (class "Default")
      (node (ref "J100") (pin "7") (pinfunction "7_7") (pintype "passive"))
    )
    (net (code "157") (name "unconnected-(J100-Pad8)") (class "Default")
      (node (ref "J100") (pin "8") (pinfunction "8_8") (pintype "passive"))
    )
    (net (code "158") (name "unconnected-(J300-PadID)") (class "Default")
      (node (ref "J300") (pin "ID") (pinfunction "ID_ID") (pintype "bidirectional"))
    )
    (net (code "159") (name "unconnected-(J301-Pad7)") (class "Default")
      (node (ref "J301") (pin "7") (pinfunction "7_7") (pintype "passive"))
    )
    (net (code "160") (name "unconnected-(J301-Pad8)") (class "Default")
      (node (ref "J301") (pin "8") (pinfunction "8_8") (pintype "passive"))
    )
    (net (code "161") (name "unconnected-(X300-GND-Pad2)") (class "Default")
      (node (ref "X300") (pin "2") (pinfunction "GND_2") (pintype "passive"))
    )
    (net (code "162") (name "unconnected-(X300-GND-Pad4)") (class "Default")
      (node (ref "X300") (pin "4") (pinfunction "GND_4") (pintype "passive"))
    )
  )
)
